# LinTempCont_4ch_V1_1.net
KiCad netlist of a schematic drawn in EAGLE
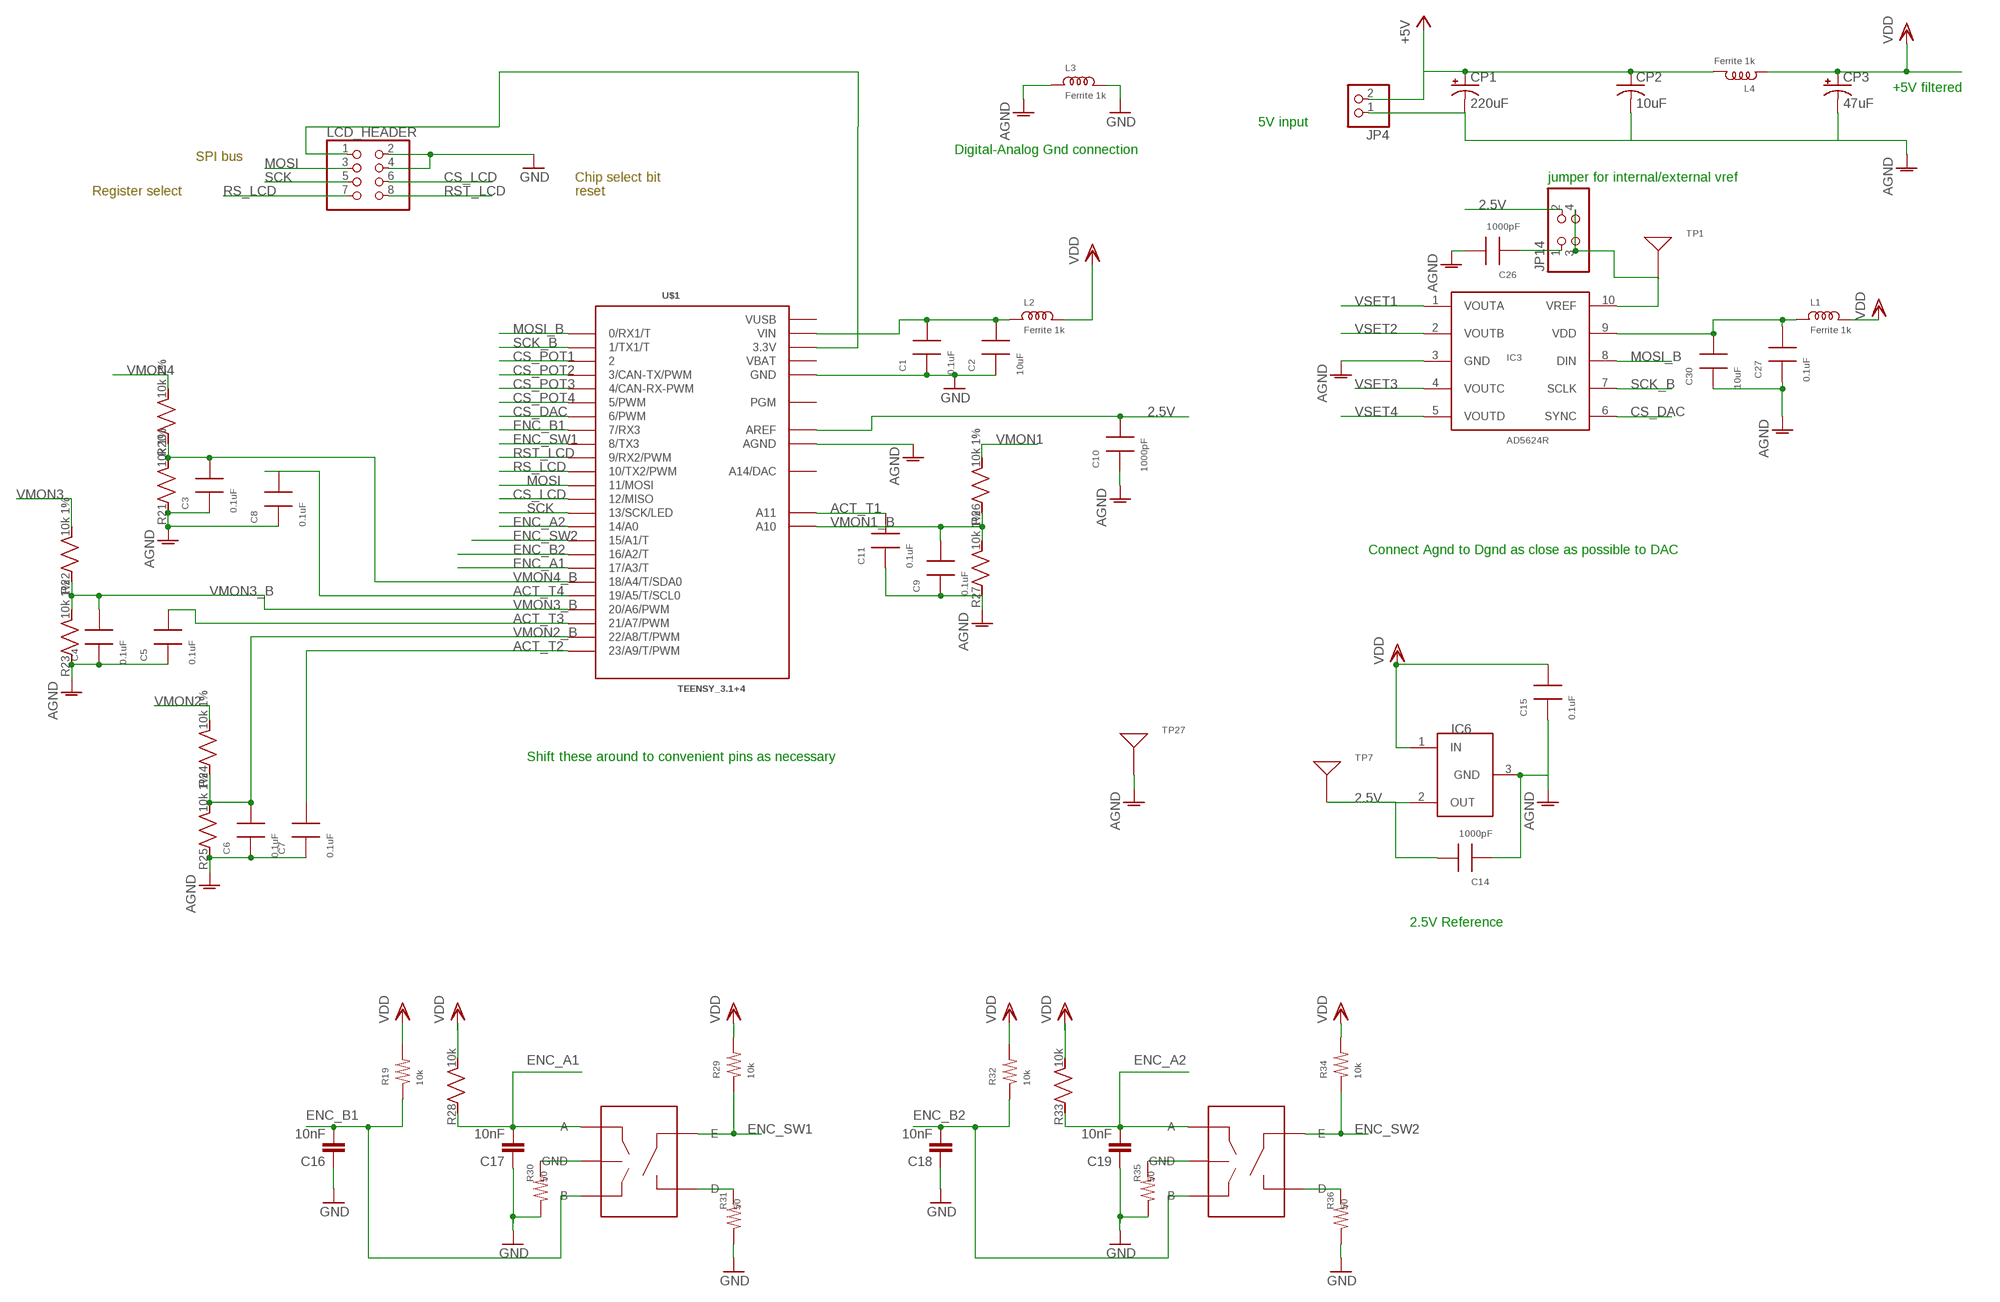
[diagram p0: schematic, sheet 1]
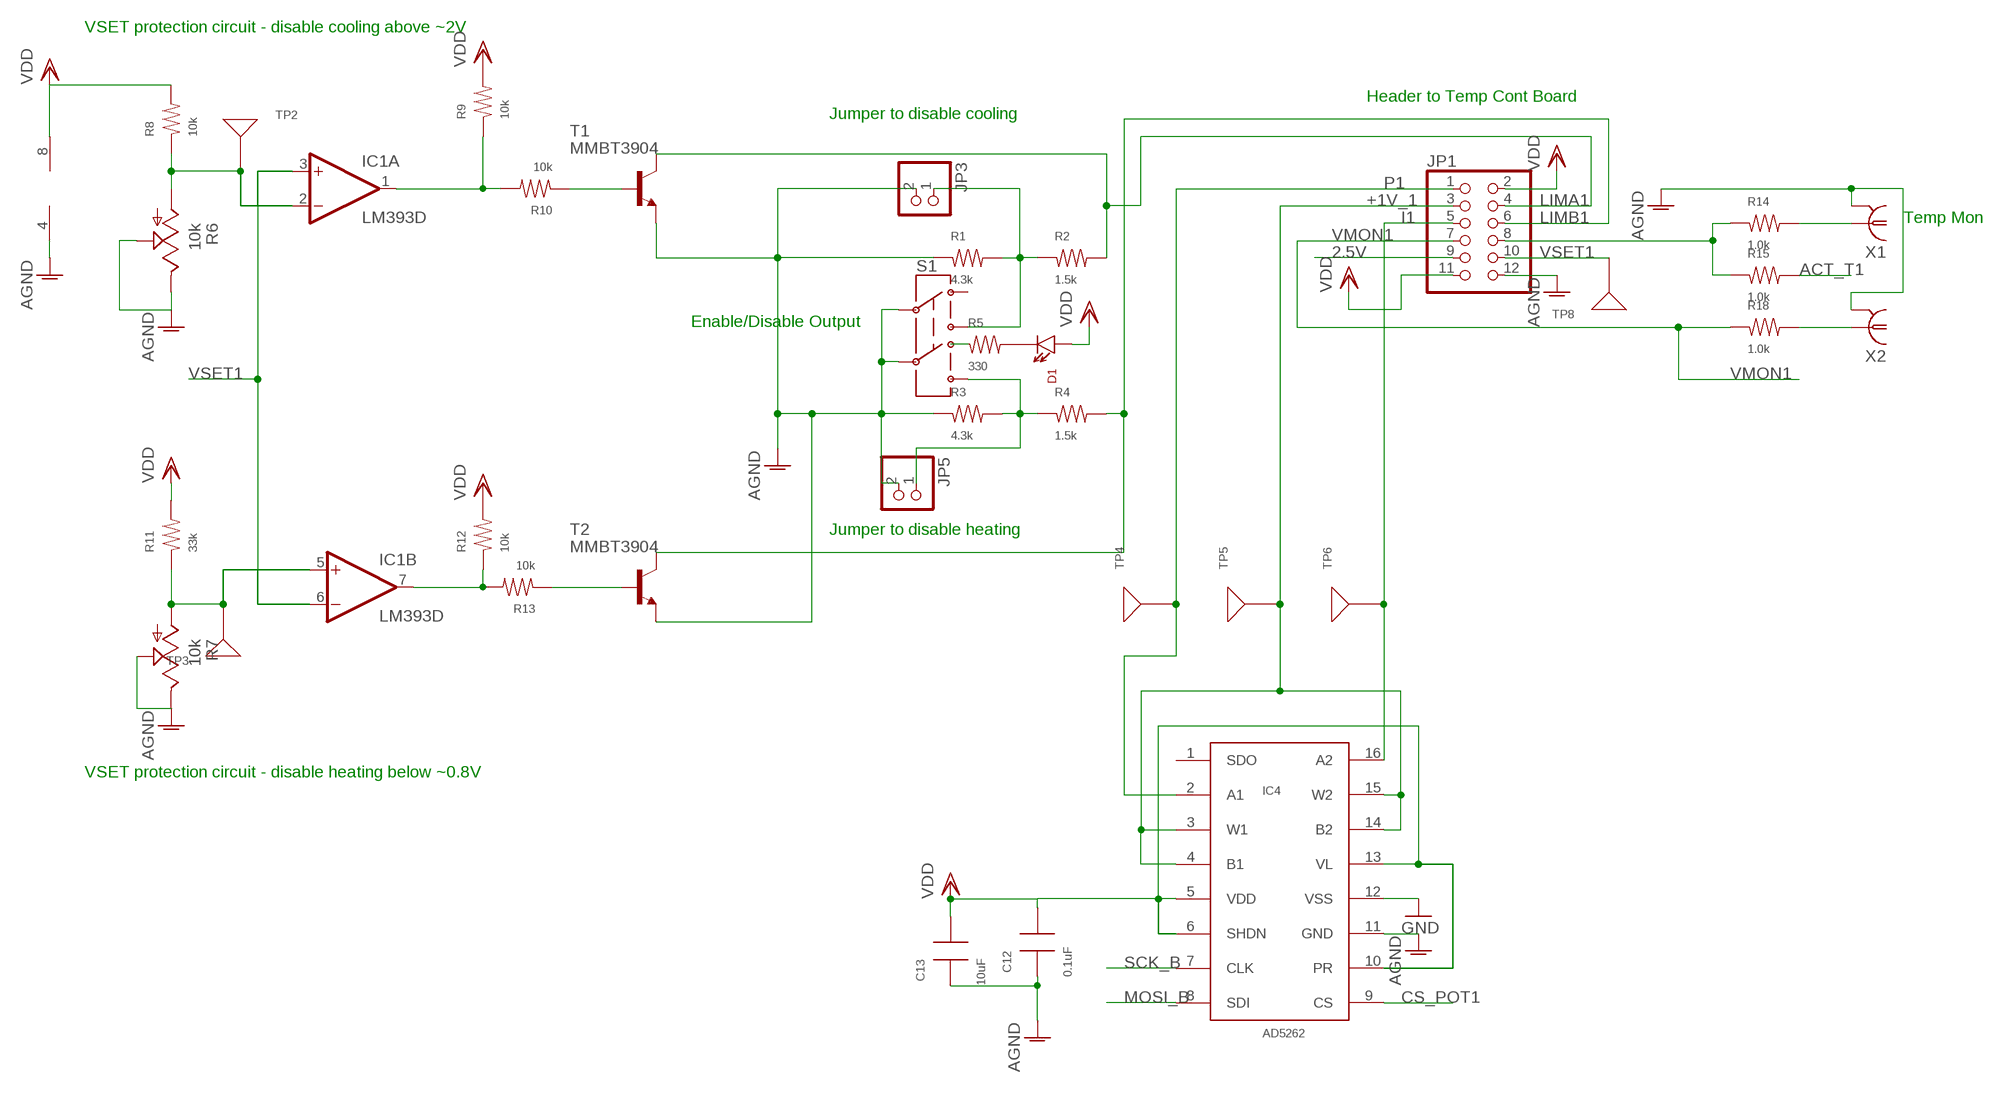
[diagram p1: schematic, sheet 2]
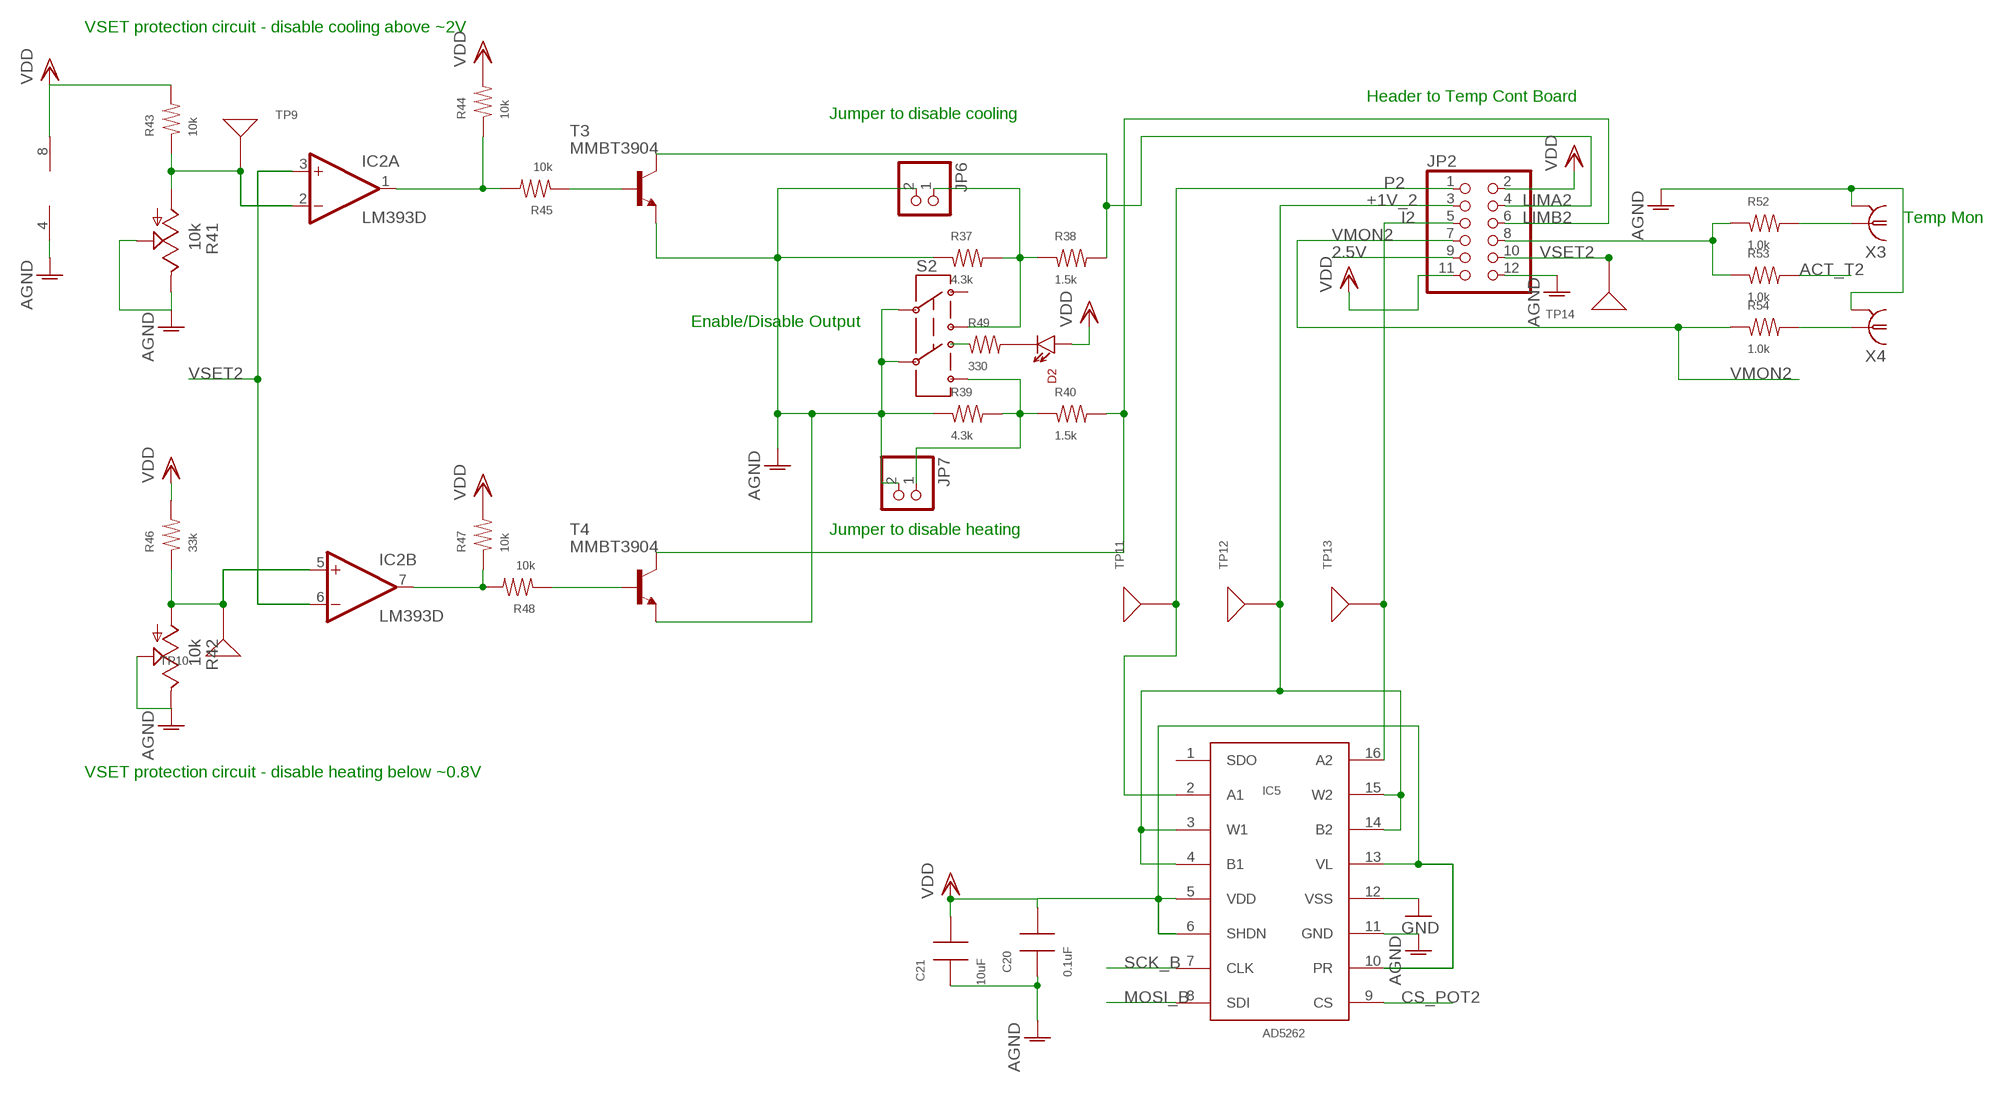
[diagram p2: schematic, sheet 3]
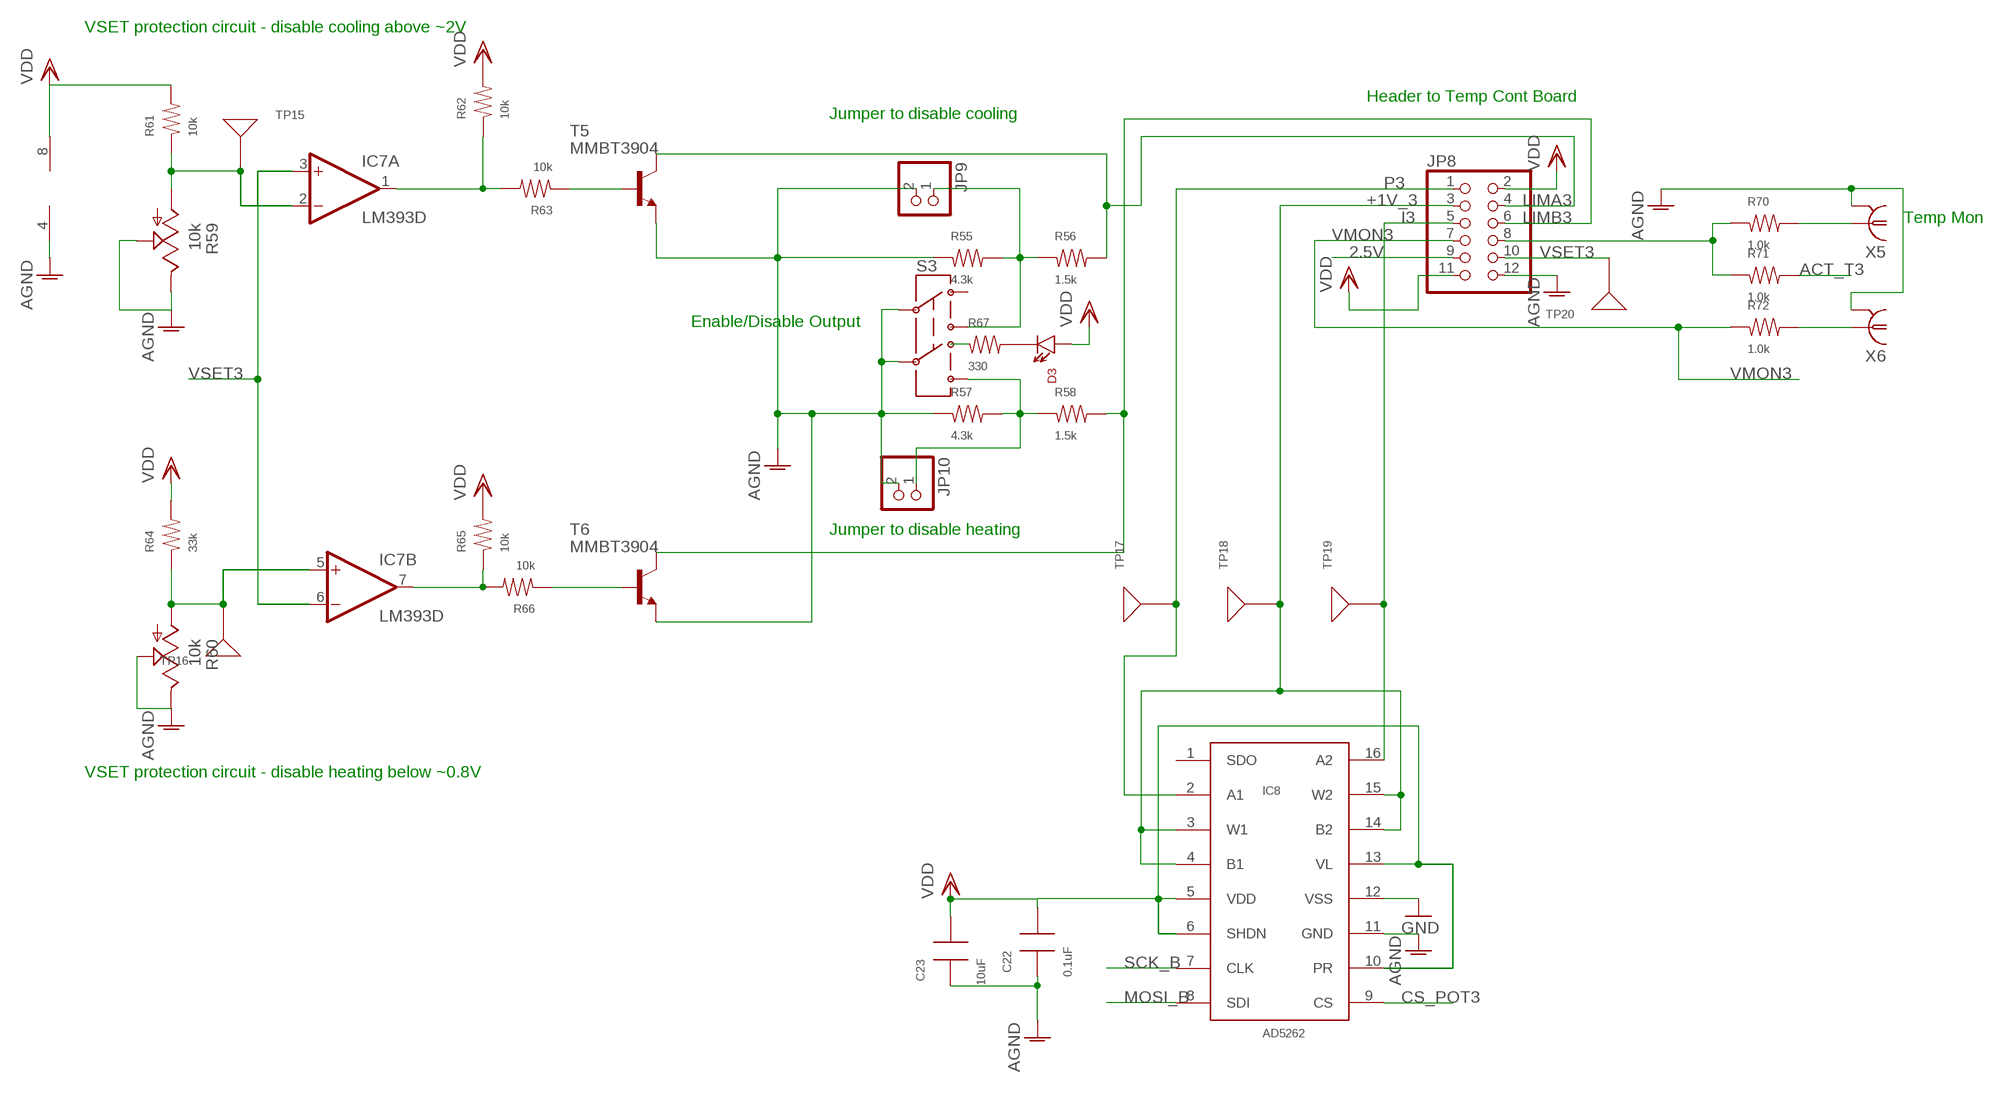
[diagram p3: schematic, sheet 4]
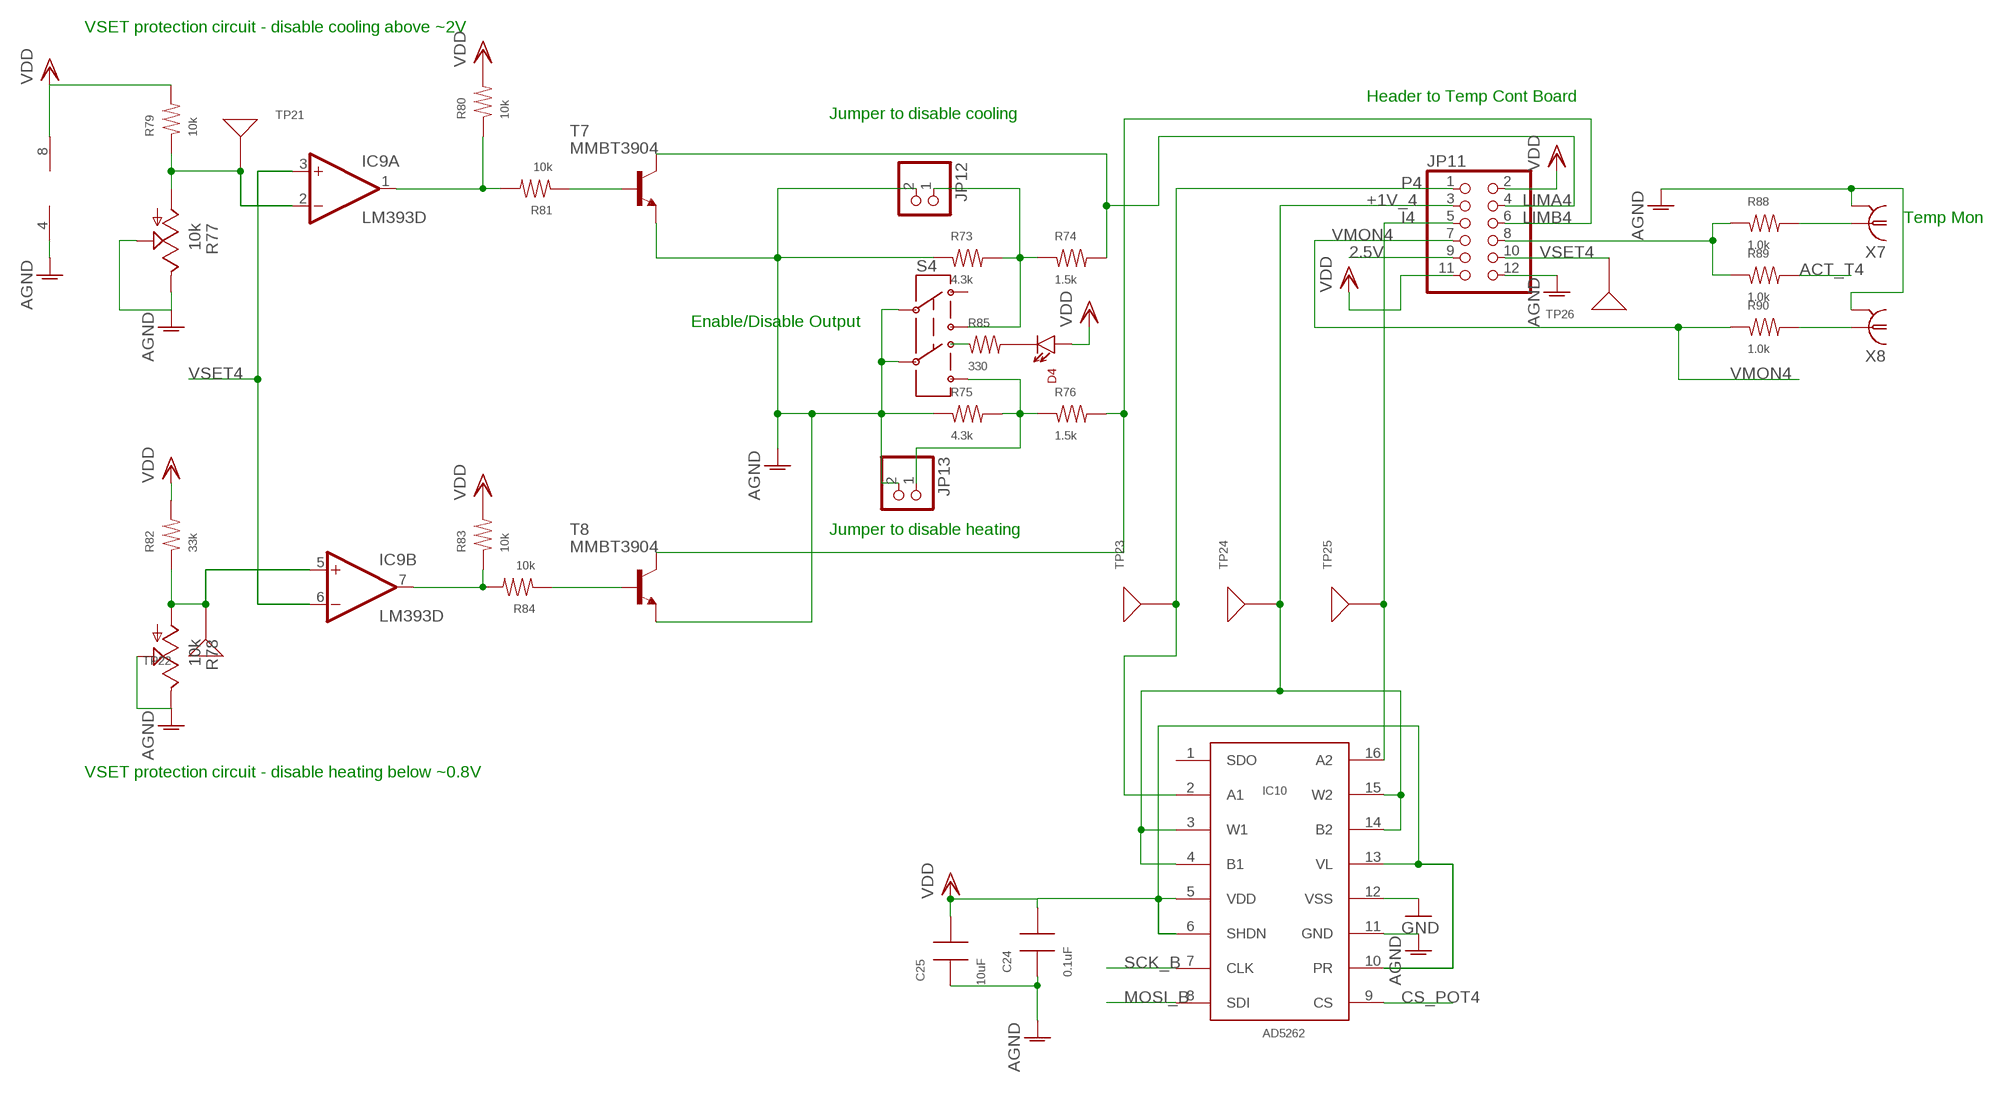
[diagram p4: schematic, sheet 5]

(export (version "E")
  (design (tool "Eeschema 10.0.6"))
  (components
    (comp (ref "C12")
      (value "0.1uF")
      (footprint "eagle-import:0603")
      (libsource (lib "eagle-import") (part "CAP0603"))
    )
    (comp (ref "C13")
      (value "10uF")
      (footprint "eagle-import:0805")
      (libsource (lib "eagle-import") (part "CAP0805"))
    )
    (comp (ref "D1")
      (value "LED/MINI-IND")
      (footprint "eagle-import:HLMP--F0010")
      (libsource (lib "eagle-import") (part "LED/MINI-IND"))
    )
    (comp (ref "IC1")
      (value "LM393D")
      (footprint "eagle-import:SO08")
      (libsource (lib "eagle-import") (part "LM393D"))
    )
    (comp (ref "IC4")
      (value "AD5262")
      (footprint "eagle-import:TSSOP16")
      (libsource (lib "eagle-import") (part "AD5262"))
    )
    (comp (ref "JP1")
      (value "PINHD-2X6/90")
      (footprint "eagle-import:2X06_90")
      (libsource (lib "eagle-import") (part "PINHD-2X6/90"))
    )
    (comp (ref "JP3")
      (value "PINHD-1X2")
      (footprint "eagle-import:1X02")
      (libsource (lib "eagle-import") (part "PINHD-1X2"))
    )
    (comp (ref "JP5")
      (value "PINHD-1X2")
      (footprint "eagle-import:1X02")
      (libsource (lib "eagle-import") (part "PINHD-1X2"))
    )
    (comp (ref "R1")
      (value "4.3k")
      (footprint "eagle-import:0603")
      (libsource (lib "eagle-import") (part "RES0603"))
    )
    (comp (ref "R2")
      (value "1.5k")
      (footprint "eagle-import:0603")
      (libsource (lib "eagle-import") (part "RES0603"))
    )
    (comp (ref "R3")
      (value "4.3k")
      (footprint "eagle-import:0603")
      (libsource (lib "eagle-import") (part "RES0603"))
    )
    (comp (ref "R4")
      (value "1.5k")
      (footprint "eagle-import:0603")
      (libsource (lib "eagle-import") (part "RES0603"))
    )
    (comp (ref "R5")
      (value "330")
      (footprint "eagle-import:0603")
      (libsource (lib "eagle-import") (part "RES0603"))
    )
    (comp (ref "R6")
      (value "10k")
      (footprint "eagle-import:64WPOT")
      (libsource (lib "eagle-import") (part "MODEL64_TRIMPOT/TOP-ADJ"))
    )
    (comp (ref "R7")
      (value "10k")
      (footprint "eagle-import:64WPOT")
      (libsource (lib "eagle-import") (part "MODEL64_TRIMPOT/TOP-ADJ"))
    )
    (comp (ref "R8")
      (value "10k")
      (footprint "eagle-import:0603")
      (libsource (lib "eagle-import") (part "RES0603"))
    )
    (comp (ref "R9")
      (value "10k")
      (footprint "eagle-import:0603")
      (libsource (lib "eagle-import") (part "RES0603"))
    )
    (comp (ref "R10")
      (value "10k")
      (footprint "eagle-import:0603")
      (libsource (lib "eagle-import") (part "RES0603"))
    )
    (comp (ref "R11")
      (value "33k")
      (footprint "eagle-import:0603")
      (libsource (lib "eagle-import") (part "RES0603"))
    )
    (comp (ref "R12")
      (value "10k")
      (footprint "eagle-import:0603")
      (libsource (lib "eagle-import") (part "RES0603"))
    )
    (comp (ref "R13")
      (value "10k")
      (footprint "eagle-import:0603")
      (libsource (lib "eagle-import") (part "RES0603"))
    )
    (comp (ref "R14")
      (value "1.0k")
      (footprint "eagle-import:0603")
      (libsource (lib "eagle-import") (part "RES0603"))
    )
    (comp (ref "R15")
      (value "1.0k")
      (footprint "eagle-import:0603")
      (libsource (lib "eagle-import") (part "RES0603"))
    )
    (comp (ref "R18")
      (value "1.0k")
      (footprint "eagle-import:0603")
      (libsource (lib "eagle-import") (part "RES0603"))
    )
    (comp (ref "S1")
      (value "SWITCH-DPDT/VER")
      (footprint "eagle-import:E-SWITCH-100-M7")
      (libsource (lib "eagle-import") (part "SWITCH-DPDT/VER"))
    )
    (comp (ref "T1")
      (value "MMBT3904")
      (footprint "eagle-import:SOT-23")
      (libsource (lib "eagle-import") (part "MMBT3904"))
    )
    (comp (ref "T2")
      (value "MMBT3904")
      (footprint "eagle-import:SOT-23")
      (libsource (lib "eagle-import") (part "MMBT3904"))
    )
    (comp (ref "TP2")
      (value "TESTPT")
      (footprint "eagle-import:1206TESTPAD")
      (libsource (lib "eagle-import") (part "TESTPT"))
    )
    (comp (ref "TP3")
      (value "TESTPT")
      (footprint "eagle-import:1206TESTPAD")
      (libsource (lib "eagle-import") (part "TESTPT"))
    )
    (comp (ref "TP4")
      (value "TESTPT")
      (footprint "eagle-import:1206TESTPAD")
      (libsource (lib "eagle-import") (part "TESTPT"))
    )
    (comp (ref "TP5")
      (value "TESTPT")
      (footprint "eagle-import:1206TESTPAD")
      (libsource (lib "eagle-import") (part "TESTPT"))
    )
    (comp (ref "TP6")
      (value "TESTPT")
      (footprint "eagle-import:1206TESTPAD")
      (libsource (lib "eagle-import") (part "TESTPT"))
    )
    (comp (ref "TP8")
      (value "TESTPT")
      (footprint "eagle-import:1206TESTPAD")
      (libsource (lib "eagle-import") (part "TESTPT"))
    )
    (comp (ref "X1")
      (value "BNC-H")
      (footprint "eagle-import:BNC90")
      (libsource (lib "eagle-import") (part "BNC-H"))
    )
    (comp (ref "X2")
      (value "BNC-H")
      (footprint "eagle-import:BNC90")
      (libsource (lib "eagle-import") (part "BNC-H"))
    )
    (comp (ref "C22")
      (value "0.1uF")
      (footprint "eagle-import:0603")
      (libsource (lib "eagle-import") (part "CAP0603"))
    )
    (comp (ref "C23")
      (value "10uF")
      (footprint "eagle-import:0805")
      (libsource (lib "eagle-import") (part "CAP0805"))
    )
    (comp (ref "D3")
      (value "LED/MINI-IND")
      (footprint "eagle-import:HLMP--F0010")
      (libsource (lib "eagle-import") (part "LED/MINI-IND"))
    )
    (comp (ref "IC7")
      (value "LM393D")
      (footprint "eagle-import:SO08")
      (libsource (lib "eagle-import") (part "LM393D"))
    )
    (comp (ref "IC8")
      (value "AD5262")
      (footprint "eagle-import:TSSOP16")
      (libsource (lib "eagle-import") (part "AD5262"))
    )
    (comp (ref "JP8")
      (value "PINHD-2X6/90")
      (footprint "eagle-import:2X06_90")
      (libsource (lib "eagle-import") (part "PINHD-2X6/90"))
    )
    (comp (ref "JP9")
      (value "PINHD-1X2")
      (footprint "eagle-import:1X02")
      (libsource (lib "eagle-import") (part "PINHD-1X2"))
    )
    (comp (ref "JP10")
      (value "PINHD-1X2")
      (footprint "eagle-import:1X02")
      (libsource (lib "eagle-import") (part "PINHD-1X2"))
    )
    (comp (ref "R55")
      (value "4.3k")
      (footprint "eagle-import:0603")
      (libsource (lib "eagle-import") (part "RES0603"))
    )
    (comp (ref "R56")
      (value "1.5k")
      (footprint "eagle-import:0603")
      (libsource (lib "eagle-import") (part "RES0603"))
    )
    (comp (ref "R57")
      (value "4.3k")
      (footprint "eagle-import:0603")
      (libsource (lib "eagle-import") (part "RES0603"))
    )
    (comp (ref "R58")
      (value "1.5k")
      (footprint "eagle-import:0603")
      (libsource (lib "eagle-import") (part "RES0603"))
    )
    (comp (ref "R59")
      (value "10k")
      (footprint "eagle-import:64WPOT")
      (libsource (lib "eagle-import") (part "MODEL64_TRIMPOT/TOP-ADJ"))
    )
    (comp (ref "R60")
      (value "10k")
      (footprint "eagle-import:64WPOT")
      (libsource (lib "eagle-import") (part "MODEL64_TRIMPOT/TOP-ADJ"))
    )
    (comp (ref "R61")
      (value "10k")
      (footprint "eagle-import:0603")
      (libsource (lib "eagle-import") (part "RES0603"))
    )
    (comp (ref "R62")
      (value "10k")
      (footprint "eagle-import:0603")
      (libsource (lib "eagle-import") (part "RES0603"))
    )
    (comp (ref "R63")
      (value "10k")
      (footprint "eagle-import:0603")
      (libsource (lib "eagle-import") (part "RES0603"))
    )
    (comp (ref "R64")
      (value "33k")
      (footprint "eagle-import:0603")
      (libsource (lib "eagle-import") (part "RES0603"))
    )
    (comp (ref "R65")
      (value "10k")
      (footprint "eagle-import:0603")
      (libsource (lib "eagle-import") (part "RES0603"))
    )
    (comp (ref "R66")
      (value "10k")
      (footprint "eagle-import:0603")
      (libsource (lib "eagle-import") (part "RES0603"))
    )
    (comp (ref "R67")
      (value "330")
      (footprint "eagle-import:0603")
      (libsource (lib "eagle-import") (part "RES0603"))
    )
    (comp (ref "R70")
      (value "1.0k")
      (footprint "eagle-import:0603")
      (libsource (lib "eagle-import") (part "RES0603"))
    )
    (comp (ref "R71")
      (value "1.0k")
      (footprint "eagle-import:0603")
      (libsource (lib "eagle-import") (part "RES0603"))
    )
    (comp (ref "R72")
      (value "1.0k")
      (footprint "eagle-import:0603")
      (libsource (lib "eagle-import") (part "RES0603"))
    )
    (comp (ref "S3")
      (value "SWITCH-DPDT/VER")
      (footprint "eagle-import:E-SWITCH-100-M7")
      (libsource (lib "eagle-import") (part "SWITCH-DPDT/VER"))
    )
    (comp (ref "T5")
      (value "MMBT3904")
      (footprint "eagle-import:SOT-23")
      (libsource (lib "eagle-import") (part "MMBT3904"))
    )
    (comp (ref "T6")
      (value "MMBT3904")
      (footprint "eagle-import:SOT-23")
      (libsource (lib "eagle-import") (part "MMBT3904"))
    )
    (comp (ref "TP15")
      (value "TESTPT")
      (footprint "eagle-import:1206TESTPAD")
      (libsource (lib "eagle-import") (part "TESTPT"))
    )
    (comp (ref "TP16")
      (value "TESTPT")
      (footprint "eagle-import:1206TESTPAD")
      (libsource (lib "eagle-import") (part "TESTPT"))
    )
    (comp (ref "TP17")
      (value "TESTPT")
      (footprint "eagle-import:1206TESTPAD")
      (libsource (lib "eagle-import") (part "TESTPT"))
    )
    (comp (ref "TP18")
      (value "TESTPT")
      (footprint "eagle-import:1206TESTPAD")
      (libsource (lib "eagle-import") (part "TESTPT"))
    )
    (comp (ref "TP19")
      (value "TESTPT")
      (footprint "eagle-import:1206TESTPAD")
      (libsource (lib "eagle-import") (part "TESTPT"))
    )
    (comp (ref "TP20")
      (value "TESTPT")
      (footprint "eagle-import:1206TESTPAD")
      (libsource (lib "eagle-import") (part "TESTPT"))
    )
    (comp (ref "X5")
      (value "BNC-H")
      (footprint "eagle-import:BNC90")
      (libsource (lib "eagle-import") (part "BNC-H"))
    )
    (comp (ref "X6")
      (value "BNC-H")
      (footprint "eagle-import:BNC90")
      (libsource (lib "eagle-import") (part "BNC-H"))
    )
    (comp (ref "C20")
      (value "0.1uF")
      (footprint "eagle-import:0603")
      (libsource (lib "eagle-import") (part "CAP0603"))
    )
    (comp (ref "C21")
      (value "10uF")
      (footprint "eagle-import:0805")
      (libsource (lib "eagle-import") (part "CAP0805"))
    )
    (comp (ref "D2")
      (value "LED/MINI-IND")
      (footprint "eagle-import:HLMP--F0010")
      (libsource (lib "eagle-import") (part "LED/MINI-IND"))
    )
    (comp (ref "IC2")
      (value "LM393D")
      (footprint "eagle-import:SO08")
      (libsource (lib "eagle-import") (part "LM393D"))
    )
    (comp (ref "IC5")
      (value "AD5262")
      (footprint "eagle-import:TSSOP16")
      (libsource (lib "eagle-import") (part "AD5262"))
    )
    (comp (ref "JP2")
      (value "PINHD-2X6/90")
      (footprint "eagle-import:2X06_90")
      (libsource (lib "eagle-import") (part "PINHD-2X6/90"))
    )
    (comp (ref "JP6")
      (value "PINHD-1X2")
      (footprint "eagle-import:1X02")
      (libsource (lib "eagle-import") (part "PINHD-1X2"))
    )
    (comp (ref "JP7")
      (value "PINHD-1X2")
      (footprint "eagle-import:1X02")
      (libsource (lib "eagle-import") (part "PINHD-1X2"))
    )
    (comp (ref "R37")
      (value "4.3k")
      (footprint "eagle-import:0603")
      (libsource (lib "eagle-import") (part "RES0603"))
    )
    (comp (ref "R38")
      (value "1.5k")
      (footprint "eagle-import:0603")
      (libsource (lib "eagle-import") (part "RES0603"))
    )
    (comp (ref "R39")
      (value "4.3k")
      (footprint "eagle-import:0603")
      (libsource (lib "eagle-import") (part "RES0603"))
    )
    (comp (ref "R40")
      (value "1.5k")
      (footprint "eagle-import:0603")
      (libsource (lib "eagle-import") (part "RES0603"))
    )
    (comp (ref "R41")
      (value "10k")
      (footprint "eagle-import:64WPOT")
      (libsource (lib "eagle-import") (part "MODEL64_TRIMPOT/TOP-ADJ"))
    )
    (comp (ref "R42")
      (value "10k")
      (footprint "eagle-import:64WPOT")
      (libsource (lib "eagle-import") (part "MODEL64_TRIMPOT/TOP-ADJ"))
    )
    (comp (ref "R43")
      (value "10k")
      (footprint "eagle-import:0603")
      (libsource (lib "eagle-import") (part "RES0603"))
    )
    (comp (ref "R44")
      (value "10k")
      (footprint "eagle-import:0603")
      (libsource (lib "eagle-import") (part "RES0603"))
    )
    (comp (ref "R45")
      (value "10k")
      (footprint "eagle-import:0603")
      (libsource (lib "eagle-import") (part "RES0603"))
    )
    (comp (ref "R46")
      (value "33k")
      (footprint "eagle-import:0603")
      (libsource (lib "eagle-import") (part "RES0603"))
    )
    (comp (ref "R47")
      (value "10k")
      (footprint "eagle-import:0603")
      (libsource (lib "eagle-import") (part "RES0603"))
    )
    (comp (ref "R48")
      (value "10k")
      (footprint "eagle-import:0603")
      (libsource (lib "eagle-import") (part "RES0603"))
    )
    (comp (ref "R49")
      (value "330")
      (footprint "eagle-import:0603")
      (libsource (lib "eagle-import") (part "RES0603"))
    )
    (comp (ref "R52")
      (value "1.0k")
      (footprint "eagle-import:0603")
      (libsource (lib "eagle-import") (part "RES0603"))
    )
    (comp (ref "R53")
      (value "1.0k")
      (footprint "eagle-import:0603")
      (libsource (lib "eagle-import") (part "RES0603"))
    )
    (comp (ref "R54")
      (value "1.0k")
      (footprint "eagle-import:0603")
      (libsource (lib "eagle-import") (part "RES0603"))
    )
    (comp (ref "S2")
      (value "SWITCH-DPDT/VER")
      (footprint "eagle-import:E-SWITCH-100-M7")
      (libsource (lib "eagle-import") (part "SWITCH-DPDT/VER"))
    )
    (comp (ref "T3")
      (value "MMBT3904")
      (footprint "eagle-import:SOT-23")
      (libsource (lib "eagle-import") (part "MMBT3904"))
    )
    (comp (ref "T4")
      (value "MMBT3904")
      (footprint "eagle-import:SOT-23")
      (libsource (lib "eagle-import") (part "MMBT3904"))
    )
    (comp (ref "TP9")
      (value "TESTPT")
      (footprint "eagle-import:1206TESTPAD")
      (libsource (lib "eagle-import") (part "TESTPT"))
    )
    (comp (ref "TP10")
      (value "TESTPT")
      (footprint "eagle-import:1206TESTPAD")
      (libsource (lib "eagle-import") (part "TESTPT"))
    )
    (comp (ref "TP11")
      (value "TESTPT")
      (footprint "eagle-import:1206TESTPAD")
      (libsource (lib "eagle-import") (part "TESTPT"))
    )
    (comp (ref "TP12")
      (value "TESTPT")
      (footprint "eagle-import:1206TESTPAD")
      (libsource (lib "eagle-import") (part "TESTPT"))
    )
    (comp (ref "TP13")
      (value "TESTPT")
      (footprint "eagle-import:1206TESTPAD")
      (libsource (lib "eagle-import") (part "TESTPT"))
    )
    (comp (ref "TP14")
      (value "TESTPT")
      (footprint "eagle-import:1206TESTPAD")
      (libsource (lib "eagle-import") (part "TESTPT"))
    )
    (comp (ref "X3")
      (value "BNC-H")
      (footprint "eagle-import:BNC90")
      (libsource (lib "eagle-import") (part "BNC-H"))
    )
    (comp (ref "X4")
      (value "BNC-H")
      (footprint "eagle-import:BNC90")
      (libsource (lib "eagle-import") (part "BNC-H"))
    )
    (comp (ref "C1")
      (value "0.1uF")
      (footprint "eagle-import:0603")
      (libsource (lib "eagle-import") (part "CAP0603"))
    )
    (comp (ref "C2")
      (value "10uF")
      (footprint "eagle-import:0805")
      (libsource (lib "eagle-import") (part "CAP0805"))
    )
    (comp (ref "C3")
      (value "0.1uF")
      (footprint "eagle-import:0603")
      (libsource (lib "eagle-import") (part "CAP0603"))
    )
    (comp (ref "C4")
      (value "0.1uF")
      (footprint "eagle-import:0603")
      (libsource (lib "eagle-import") (part "CAP0603"))
    )
    (comp (ref "C5")
      (value "0.1uF")
      (footprint "eagle-import:0603")
      (libsource (lib "eagle-import") (part "CAP0603"))
    )
    (comp (ref "C6")
      (value "0.1uF")
      (footprint "eagle-import:0603")
      (libsource (lib "eagle-import") (part "CAP0603"))
    )
    (comp (ref "C7")
      (value "0.1uF")
      (footprint "eagle-import:0603")
      (libsource (lib "eagle-import") (part "CAP0603"))
    )
    (comp (ref "C8")
      (value "0.1uF")
      (footprint "eagle-import:0603")
      (libsource (lib "eagle-import") (part "CAP0603"))
    )
    (comp (ref "C9")
      (value "0.1uF")
      (footprint "eagle-import:0603")
      (libsource (lib "eagle-import") (part "CAP0603"))
    )
    (comp (ref "C10")
      (value "1000pF")
      (footprint "eagle-import:0603")
      (libsource (lib "eagle-import") (part "CAP0603"))
    )
    (comp (ref "C11")
      (value "0.1uF")
      (footprint "eagle-import:0603")
      (libsource (lib "eagle-import") (part "CAP0603"))
    )
    (comp (ref "C14")
      (value "1000pF")
      (footprint "eagle-import:0603")
      (libsource (lib "eagle-import") (part "CAP0603"))
    )
    (comp (ref "C15")
      (value "0.1uF")
      (footprint "eagle-import:0603")
      (libsource (lib "eagle-import") (part "CAP0603"))
    )
    (comp (ref "C16")
      (value "10nF")
      (footprint "eagle-import:C0603")
      (libsource (lib "eagle-import") (part "C-EUC0603"))
    )
    (comp (ref "C17")
      (value "10nF")
      (footprint "eagle-import:C0603")
      (libsource (lib "eagle-import") (part "C-EUC0603"))
    )
    (comp (ref "C18")
      (value "10nF")
      (footprint "eagle-import:C0603")
      (libsource (lib "eagle-import") (part "C-EUC0603"))
    )
    (comp (ref "C19")
      (value "10nF")
      (footprint "eagle-import:C0603")
      (libsource (lib "eagle-import") (part "C-EUC0603"))
    )
    (comp (ref "C26")
      (value "1000pF")
      (footprint "eagle-import:0603")
      (libsource (lib "eagle-import") (part "CAP0603"))
    )
    (comp (ref "C27")
      (value "0.1uF")
      (footprint "eagle-import:0603")
      (libsource (lib "eagle-import") (part "CAP0603"))
    )
    (comp (ref "C30")
      (value "10uF")
      (footprint "eagle-import:0805")
      (libsource (lib "eagle-import") (part "CAP0805"))
    )
    (comp (ref "CP1")
      (value "220uF")
      (footprint "eagle-import:PANASONIC_F")
      (libsource (lib "eagle-import") (part "CPOL-USF"))
    )
    (comp (ref "CP2")
      (value "10uF")
      (footprint "eagle-import:C0805K")
      (libsource (lib "eagle-import") (part "C-USC0805K"))
    )
    (comp (ref "CP3")
      (value "47uF")
      (footprint "eagle-import:CT7343")
      (libsource (lib "eagle-import") (part "CPOL-USCT7343"))
    )
    (comp (ref "ENC1")
      (value "PEC09")
      (footprint "eagle-import:PEC092320FS")
      (libsource (lib "eagle-import") (part "PEC09"))
    )
    (comp (ref "ENC2")
      (value "PEC09")
      (footprint "eagle-import:PEC092320FS")
      (libsource (lib "eagle-import") (part "PEC09"))
    )
    (comp (ref "IC3")
      (value "AD5624R")
      (footprint "eagle-import:MSOP10")
      (libsource (lib "eagle-import") (part "AD5624R"))
    )
    (comp (ref "IC6")
      (value "TS6001")
      (footprint "eagle-import:SOT-23")
      (libsource (lib "eagle-import") (part "TS6001"))
    )
    (comp (ref "JP4")
      (value "SCRWTRM-1X2")
      (footprint "eagle-import:1X02_SCRWTRM")
      (libsource (lib "eagle-import") (part "SCRWTRM-1X2"))
    )
    (comp (ref "JP14")
      (value "PINHD-2X2")
      (footprint "eagle-import:2X02")
      (libsource (lib "eagle-import") (part "PINHD-2X2"))
    )
    (comp (ref "L1")
      (value "Ferrite 1k")
      (footprint "eagle-import:0805")
      (libsource (lib "eagle-import") (part "INDUCTOR-0805"))
    )
    (comp (ref "L2")
      (value "Ferrite 1k")
      (footprint "eagle-import:0805")
      (libsource (lib "eagle-import") (part "INDUCTOR-0805"))
    )
    (comp (ref "L3")
      (value "Ferrite 1k")
      (footprint "eagle-import:0805")
      (libsource (lib "eagle-import") (part "INDUCTOR-0805"))
    )
    (comp (ref "L4")
      (value "Ferrite 1k")
      (footprint "eagle-import:0805")
      (libsource (lib "eagle-import") (part "INDUCTOR-0805"))
    )
    (comp (ref "LCD_HEADER")
      (value "PINHD-2X4-SHROUD")
      (footprint "eagle-import:ML08")
      (libsource (lib "eagle-import") (part "PINHD-2X4-SHROUD"))
    )
    (comp (ref "R19")
      (value "10k")
      (footprint "eagle-import:0603")
      (libsource (lib "eagle-import") (part "RES0603"))
    )
    (comp (ref "R20")
      (value "10k 1%")
      (footprint "eagle-import:R_0603")
      (libsource (lib "eagle-import") (part "R_SMDR0603"))
    )
    (comp (ref "R21")
      (value "10k 1%")
      (footprint "eagle-import:R_0603")
      (libsource (lib "eagle-import") (part "R_SMDR0603"))
    )
    (comp (ref "R22")
      (value "10k 1%")
      (footprint "eagle-import:R_0603")
      (libsource (lib "eagle-import") (part "R_SMDR0603"))
    )
    (comp (ref "R23")
      (value "10k 1%")
      (footprint "eagle-import:R_0603")
      (libsource (lib "eagle-import") (part "R_SMDR0603"))
    )
    (comp (ref "R24")
      (value "10k 1%")
      (footprint "eagle-import:R_0603")
      (libsource (lib "eagle-import") (part "R_SMDR0603"))
    )
    (comp (ref "R25")
      (value "10k 1%")
      (footprint "eagle-import:R_0603")
      (libsource (lib "eagle-import") (part "R_SMDR0603"))
    )
    (comp (ref "R26")
      (value "10k 1%")
      (footprint "eagle-import:R_0603")
      (libsource (lib "eagle-import") (part "R_SMDR0603"))
    )
    (comp (ref "R27")
      (value "10k 1%")
      (footprint "eagle-import:R_0603")
      (libsource (lib "eagle-import") (part "R_SMDR0603"))
    )
    (comp (ref "R28")
      (value "10k")
      (footprint "eagle-import:R_0603")
      (libsource (lib "eagle-import") (part "R_SMDR0603"))
    )
    (comp (ref "R29")
      (value "10k")
      (footprint "eagle-import:0603")
      (libsource (lib "eagle-import") (part "RES0603"))
    )
    (comp (ref "R30")
      (value "50")
      (footprint "eagle-import:0603")
      (libsource (lib "eagle-import") (part "RES0603"))
    )
    (comp (ref "R31")
      (value "50")
      (footprint "eagle-import:0603")
      (libsource (lib "eagle-import") (part "RES0603"))
    )
    (comp (ref "R32")
      (value "10k")
      (footprint "eagle-import:0603")
      (libsource (lib "eagle-import") (part "RES0603"))
    )
    (comp (ref "R33")
      (value "10k")
      (footprint "eagle-import:R_0603")
      (libsource (lib "eagle-import") (part "R_SMDR0603"))
    )
    (comp (ref "R34")
      (value "10k")
      (footprint "eagle-import:0603")
      (libsource (lib "eagle-import") (part "RES0603"))
    )
    (comp (ref "R35")
      (value "50")
      (footprint "eagle-import:0603")
      (libsource (lib "eagle-import") (part "RES0603"))
    )
    (comp (ref "R36")
      (value "50")
      (footprint "eagle-import:0603")
      (libsource (lib "eagle-import") (part "RES0603"))
    )
    (comp (ref "TP1")
      (value "TESTPT")
      (footprint "eagle-import:1206TESTPAD")
      (libsource (lib "eagle-import") (part "TESTPT"))
    )
    (comp (ref "TP7")
      (value "TESTPT")
      (footprint "eagle-import:1206TESTPAD")
      (libsource (lib "eagle-import") (part "TESTPT"))
    )
    (comp (ref "TP27")
      (value "TESTPT")
      (footprint "eagle-import:1206TESTPAD")
      (libsource (lib "eagle-import") (part "TESTPT"))
    )
    (comp (ref "U$1")
      (value "TEENSY_3.1+4")
      (footprint "eagle-import:TEENSY_3.1+4")
      (libsource (lib "eagle-import") (part "TEENSY_3.1+4"))
    )
    (comp (ref "C24")
      (value "0.1uF")
      (footprint "eagle-import:0603")
      (libsource (lib "eagle-import") (part "CAP0603"))
    )
    (comp (ref "C25")
      (value "10uF")
      (footprint "eagle-import:0805")
      (libsource (lib "eagle-import") (part "CAP0805"))
    )
    (comp (ref "D4")
      (value "LED/MINI-IND")
      (footprint "eagle-import:HLMP--F0010")
      (libsource (lib "eagle-import") (part "LED/MINI-IND"))
    )
    (comp (ref "IC9")
      (value "LM393D")
      (footprint "eagle-import:SO08")
      (libsource (lib "eagle-import") (part "LM393D"))
    )
    (comp (ref "IC10")
      (value "AD5262")
      (footprint "eagle-import:TSSOP16")
      (libsource (lib "eagle-import") (part "AD5262"))
    )
    (comp (ref "JP11")
      (value "PINHD-2X6/90")
      (footprint "eagle-import:2X06_90")
      (libsource (lib "eagle-import") (part "PINHD-2X6/90"))
    )
    (comp (ref "JP12")
      (value "PINHD-1X2")
      (footprint "eagle-import:1X02")
      (libsource (lib "eagle-import") (part "PINHD-1X2"))
    )
    (comp (ref "JP13")
      (value "PINHD-1X2")
      (footprint "eagle-import:1X02")
      (libsource (lib "eagle-import") (part "PINHD-1X2"))
    )
    (comp (ref "R73")
      (value "4.3k")
      (footprint "eagle-import:0603")
      (libsource (lib "eagle-import") (part "RES0603"))
    )
    (comp (ref "R74")
      (value "1.5k")
      (footprint "eagle-import:0603")
      (libsource (lib "eagle-import") (part "RES0603"))
    )
    (comp (ref "R75")
      (value "4.3k")
      (footprint "eagle-import:0603")
      (libsource (lib "eagle-import") (part "RES0603"))
    )
    (comp (ref "R76")
      (value "1.5k")
      (footprint "eagle-import:0603")
      (libsource (lib "eagle-import") (part "RES0603"))
    )
    (comp (ref "R77")
      (value "10k")
      (footprint "eagle-import:64WPOT")
      (libsource (lib "eagle-import") (part "MODEL64_TRIMPOT/TOP-ADJ"))
    )
    (comp (ref "R78")
      (value "10k")
      (footprint "eagle-import:64WPOT")
      (libsource (lib "eagle-import") (part "MODEL64_TRIMPOT/TOP-ADJ"))
    )
    (comp (ref "R79")
      (value "10k")
      (footprint "eagle-import:0603")
      (libsource (lib "eagle-import") (part "RES0603"))
    )
    (comp (ref "R80")
      (value "10k")
      (footprint "eagle-import:0603")
      (libsource (lib "eagle-import") (part "RES0603"))
    )
    (comp (ref "R81")
      (value "10k")
      (footprint "eagle-import:0603")
      (libsource (lib "eagle-import") (part "RES0603"))
    )
    (comp (ref "R82")
      (value "33k")
      (footprint "eagle-import:0603")
      (libsource (lib "eagle-import") (part "RES0603"))
    )
    (comp (ref "R83")
      (value "10k")
      (footprint "eagle-import:0603")
      (libsource (lib "eagle-import") (part "RES0603"))
    )
    (comp (ref "R84")
      (value "10k")
      (footprint "eagle-import:0603")
      (libsource (lib "eagle-import") (part "RES0603"))
    )
    (comp (ref "R85")
      (value "330")
      (footprint "eagle-import:0603")
      (libsource (lib "eagle-import") (part "RES0603"))
    )
    (comp (ref "R88")
      (value "1.0k")
      (footprint "eagle-import:0603")
      (libsource (lib "eagle-import") (part "RES0603"))
    )
    (comp (ref "R89")
      (value "1.0k")
      (footprint "eagle-import:0603")
      (libsource (lib "eagle-import") (part "RES0603"))
    )
    (comp (ref "R90")
      (value "1.0k")
      (footprint "eagle-import:0603")
      (libsource (lib "eagle-import") (part "RES0603"))
    )
    (comp (ref "S4")
      (value "SWITCH-DPDT/VER")
      (footprint "eagle-import:E-SWITCH-100-M7")
      (libsource (lib "eagle-import") (part "SWITCH-DPDT/VER"))
    )
    (comp (ref "T7")
      (value "MMBT3904")
      (footprint "eagle-import:SOT-23")
      (libsource (lib "eagle-import") (part "MMBT3904"))
    )
    (comp (ref "T8")
      (value "MMBT3904")
      (footprint "eagle-import:SOT-23")
      (libsource (lib "eagle-import") (part "MMBT3904"))
    )
    (comp (ref "TP21")
      (value "TESTPT")
      (footprint "eagle-import:1206TESTPAD")
      (libsource (lib "eagle-import") (part "TESTPT"))
    )
    (comp (ref "TP22")
      (value "TESTPT")
      (footprint "eagle-import:1206TESTPAD")
      (libsource (lib "eagle-import") (part "TESTPT"))
    )
    (comp (ref "TP23")
      (value "TESTPT")
      (footprint "eagle-import:1206TESTPAD")
      (libsource (lib "eagle-import") (part "TESTPT"))
    )
    (comp (ref "TP24")
      (value "TESTPT")
      (footprint "eagle-import:1206TESTPAD")
      (libsource (lib "eagle-import") (part "TESTPT"))
    )
    (comp (ref "TP25")
      (value "TESTPT")
      (footprint "eagle-import:1206TESTPAD")
      (libsource (lib "eagle-import") (part "TESTPT"))
    )
    (comp (ref "TP26")
      (value "TESTPT")
      (footprint "eagle-import:1206TESTPAD")
      (libsource (lib "eagle-import") (part "TESTPT"))
    )
    (comp (ref "X7")
      (value "BNC-H")
      (footprint "eagle-import:BNC90")
      (libsource (lib "eagle-import") (part "BNC-H"))
    )
    (comp (ref "X8")
      (value "BNC-H")
      (footprint "eagle-import:BNC90")
      (libsource (lib "eagle-import") (part "BNC-H"))
    )
  )
  (nets
    (net (code "1") (name "+1V_1") (class "Default")
      (node (ref "IC4") (pin "14") (pinfunction "B2_14") (pintype "bidirectional"))
      (node (ref "IC4") (pin "15") (pinfunction "W2_15") (pintype "bidirectional"))
      (node (ref "IC4") (pin "3") (pinfunction "W1_3") (pintype "bidirectional"))
      (node (ref "IC4") (pin "4") (pinfunction "B1_4") (pintype "bidirectional"))
      (node (ref "JP1") (pin "3") (pinfunction "3_3") (pintype "passive"))
      (node (ref "TP5") (pin "P$1") (pinfunction "P$1_P$1") (pintype "bidirectional"))
    )
    (net (code "2") (name "+1V_2") (class "Default")
      (node (ref "IC5") (pin "14") (pinfunction "B2_14") (pintype "bidirectional"))
      (node (ref "IC5") (pin "15") (pinfunction "W2_15") (pintype "bidirectional"))
      (node (ref "IC5") (pin "3") (pinfunction "W1_3") (pintype "bidirectional"))
      (node (ref "IC5") (pin "4") (pinfunction "B1_4") (pintype "bidirectional"))
      (node (ref "JP2") (pin "3") (pinfunction "3_3") (pintype "passive"))
      (node (ref "TP12") (pin "P$1") (pinfunction "P$1_P$1") (pintype "bidirectional"))
    )
    (net (code "3") (name "+1V_3") (class "Default")
      (node (ref "IC8") (pin "14") (pinfunction "B2_14") (pintype "bidirectional"))
      (node (ref "IC8") (pin "15") (pinfunction "W2_15") (pintype "bidirectional"))
      (node (ref "IC8") (pin "3") (pinfunction "W1_3") (pintype "bidirectional"))
      (node (ref "IC8") (pin "4") (pinfunction "B1_4") (pintype "bidirectional"))
      (node (ref "JP8") (pin "3") (pinfunction "3_3") (pintype "passive"))
      (node (ref "TP18") (pin "P$1") (pinfunction "P$1_P$1") (pintype "bidirectional"))
    )
    (net (code "4") (name "+1V_4") (class "Default")
      (node (ref "IC10") (pin "14") (pinfunction "B2_14") (pintype "bidirectional"))
      (node (ref "IC10") (pin "15") (pinfunction "W2_15") (pintype "bidirectional"))
      (node (ref "IC10") (pin "3") (pinfunction "W1_3") (pintype "bidirectional"))
      (node (ref "IC10") (pin "4") (pinfunction "B1_4") (pintype "bidirectional"))
      (node (ref "JP11") (pin "3") (pinfunction "3_3") (pintype "passive"))
      (node (ref "TP24") (pin "P$1") (pinfunction "P$1_P$1") (pintype "bidirectional"))
    )
    (net (code "5") (name "+5V") (class "Default")
      (node (ref "CP1") (pin "+") (pinfunction "+_+") (pintype "passive"))
      (node (ref "CP2") (pin "1") (pinfunction "1_1") (pintype "passive"))
      (node (ref "JP4") (pin "2") (pinfunction "2_2") (pintype "passive"))
      (node (ref "L4") (pin "2") (pinfunction "P$2_2") (pintype "passive"))
    )
    (net (code "6") (name "2.5V") (class "Default")
      (node (ref "C10") (pin "2") (pinfunction "P$2_2") (pintype "passive"))
      (node (ref "C14") (pin "2") (pinfunction "P$2_2") (pintype "passive"))
      (node (ref "IC6") (pin "2") (pinfunction "OUT_2") (pintype "bidirectional"))
      (node (ref "JP1") (pin "9") (pinfunction "9_9") (pintype "passive"))
      (node (ref "JP11") (pin "9") (pinfunction "9_9") (pintype "passive"))
      (node (ref "JP14") (pin "2") (pinfunction "2_2") (pintype "passive"))
      (node (ref "JP2") (pin "9") (pinfunction "9_9") (pintype "passive"))
      (node (ref "JP8") (pin "9") (pinfunction "9_9") (pintype "passive"))
      (node (ref "TP7") (pin "P$1") (pinfunction "P$1_P$1") (pintype "bidirectional"))
      (node (ref "U$1") (pin "AREF") (pinfunction "AREF_AREF") (pintype "power_in"))
    )
    (net (code "7") (name "ACT_T1") (class "Default")
      (node (ref "C11") (pin "2") (pinfunction "P$2_2") (pintype "passive"))
      (node (ref "R15") (pin "2") (pinfunction "P$2_2") (pintype "passive"))
      (node (ref "U$1") (pin "A11") (pinfunction "A11_A11") (pintype "bidirectional"))
    )
    (net (code "8") (name "ACT_T2") (class "Default")
      (node (ref "C7") (pin "2") (pinfunction "P$2_2") (pintype "passive"))
      (node (ref "R53") (pin "2") (pinfunction "P$2_2") (pintype "passive"))
      (node (ref "U$1") (pin "23/A9") (pinfunction "23/A9/T/PWM_23/A9") (pintype "bidirectional"))
    )
    (net (code "9") (name "ACT_T3") (class "Default")
      (node (ref "C5") (pin "2") (pinfunction "P$2_2") (pintype "passive"))
      (node (ref "R71") (pin "2") (pinfunction "P$2_2") (pintype "passive"))
      (node (ref "U$1") (pin "21/A7") (pinfunction "21/A7/PWM_21/A7") (pintype "bidirectional"))
    )
    (net (code "10") (name "ACT_T4") (class "Default")
      (node (ref "C8") (pin "2") (pinfunction "P$2_2") (pintype "passive"))
      (node (ref "R89") (pin "2") (pinfunction "P$2_2") (pintype "passive"))
      (node (ref "U$1") (pin "19/A5") (pinfunction "19/A5/T/SCL0_19/A5") (pintype "bidirectional"))
    )
    (net (code "11") (name "AGND") (class "Default")
      (node (ref "C10") (pin "1") (pinfunction "P$1_1") (pintype "passive"))
      (node (ref "C11") (pin "1") (pinfunction "P$1_1") (pintype "passive"))
      (node (ref "C12") (pin "1") (pinfunction "P$1_1") (pintype "passive"))
      (node (ref "C13") (pin "1") (pinfunction "P$1_1") (pintype "passive"))
      (node (ref "C14") (pin "1") (pinfunction "P$1_1") (pintype "passive"))
      (node (ref "C15") (pin "1") (pinfunction "P$1_1") (pintype "passive"))
      (node (ref "C20") (pin "1") (pinfunction "P$1_1") (pintype "passive"))
      (node (ref "C21") (pin "1") (pinfunction "P$1_1") (pintype "passive"))
      (node (ref "C22") (pin "1") (pinfunction "P$1_1") (pintype "passive"))
      (node (ref "C23") (pin "1") (pinfunction "P$1_1") (pintype "passive"))
      (node (ref "C24") (pin "1") (pinfunction "P$1_1") (pintype "passive"))
      (node (ref "C25") (pin "1") (pinfunction "P$1_1") (pintype "passive"))
      (node (ref "C26") (pin "2") (pinfunction "P$2_2") (pintype "passive"))
      (node (ref "C27") (pin "1") (pinfunction "P$1_1") (pintype "passive"))
      (node (ref "C3") (pin "1") (pinfunction "P$1_1") (pintype "passive"))
      (node (ref "C30") (pin "1") (pinfunction "P$1_1") (pintype "passive"))
      (node (ref "C4") (pin "1") (pinfunction "P$1_1") (pintype "passive"))
      (node (ref "C5") (pin "1") (pinfunction "P$1_1") (pintype "passive"))
      (node (ref "C6") (pin "1") (pinfunction "P$1_1") (pintype "passive"))
      (node (ref "C7") (pin "1") (pinfunction "P$1_1") (pintype "passive"))
      (node (ref "C8") (pin "1") (pinfunction "P$1_1") (pintype "passive"))
      (node (ref "C9") (pin "1") (pinfunction "P$1_1") (pintype "passive"))
      (node (ref "CP1") (pin "-") (pinfunction "-_-") (pintype "passive"))
      (node (ref "CP2") (pin "2") (pinfunction "2_2") (pintype "passive"))
      (node (ref "CP3") (pin "-") (pinfunction "-_-") (pintype "passive"))
      (node (ref "IC1") (pin "4") (pinfunction "V-_4") (pintype "power_in"))
      (node (ref "IC10") (pin "11") (pinfunction "GND_11") (pintype "power_in"))
      (node (ref "IC2") (pin "4") (pinfunction "V-_4") (pintype "power_in"))
      (node (ref "IC3") (pin "3") (pinfunction "GND_3") (pintype "power_in"))
      (node (ref "IC4") (pin "11") (pinfunction "GND_11") (pintype "power_in"))
      (node (ref "IC5") (pin "11") (pinfunction "GND_11") (pintype "power_in"))
      (node (ref "IC6") (pin "3") (pinfunction "GND_3") (pintype "bidirectional"))
      (node (ref "IC7") (pin "4") (pinfunction "V-_4") (pintype "power_in"))
      (node (ref "IC8") (pin "11") (pinfunction "GND_11") (pintype "power_in"))
      (node (ref "IC9") (pin "4") (pinfunction "V-_4") (pintype "power_in"))
      (node (ref "JP1") (pin "12") (pinfunction "12_12") (pintype "passive"))
      (node (ref "JP10") (pin "2") (pinfunction "2_2") (pintype "passive"))
      (node (ref "JP11") (pin "12") (pinfunction "12_12") (pintype "passive"))
      (node (ref "JP12") (pin "2") (pinfunction "2_2") (pintype "passive"))
      (node (ref "JP13") (pin "2") (pinfunction "2_2") (pintype "passive"))
      (node (ref "JP2") (pin "12") (pinfunction "12_12") (pintype "passive"))
      (node (ref "JP3") (pin "2") (pinfunction "2_2") (pintype "passive"))
      (node (ref "JP4") (pin "1") (pinfunction "1_1") (pintype "passive"))
      (node (ref "JP5") (pin "2") (pinfunction "2_2") (pintype "passive"))
      (node (ref "JP6") (pin "2") (pinfunction "2_2") (pintype "passive"))
      (node (ref "JP7") (pin "2") (pinfunction "2_2") (pintype "passive"))
      (node (ref "JP8") (pin "12") (pinfunction "12_12") (pintype "passive"))
      (node (ref "JP9") (pin "2") (pinfunction "2_2") (pintype "passive"))
      (node (ref "L3") (pin "1") (pinfunction "P$1_1") (pintype "passive"))
      (node (ref "R1") (pin "1") (pinfunction "P$1_1") (pintype "passive"))
      (node (ref "R21") (pin "P$1") (pinfunction "1_P$1") (pintype "passive"))
      (node (ref "R23") (pin "P$1") (pinfunction "1_P$1") (pintype "passive"))
      (node (ref "R25") (pin "P$1") (pinfunction "1_P$1") (pintype "passive"))
      (node (ref "R27") (pin "P$1") (pinfunction "1_P$1") (pintype "passive"))
      (node (ref "R3") (pin "1") (pinfunction "P$1_1") (pintype "passive"))
      (node (ref "R37") (pin "1") (pinfunction "P$1_1") (pintype "passive"))
      (node (ref "R39") (pin "1") (pinfunction "P$1_1") (pintype "passive"))
      (node (ref "R41") (pin "P$2") (pinfunction "2_P$2") (pintype "passive"))
      (node (ref "R41") (pin "P$3") (pinfunction "3_P$3") (pintype "passive"))
      (node (ref "R42") (pin "P$2") (pinfunction "2_P$2") (pintype "passive"))
      (node (ref "R42") (pin "P$3") (pinfunction "3_P$3") (pintype "passive"))
      (node (ref "R55") (pin "1") (pinfunction "P$1_1") (pintype "passive"))
      (node (ref "R57") (pin "1") (pinfunction "P$1_1") (pintype "passive"))
      (node (ref "R59") (pin "P$2") (pinfunction "2_P$2") (pintype "passive"))
      (node (ref "R59") (pin "P$3") (pinfunction "3_P$3") (pintype "passive"))
      (node (ref "R6") (pin "P$2") (pinfunction "2_P$2") (pintype "passive"))
      (node (ref "R6") (pin "P$3") (pinfunction "3_P$3") (pintype "passive"))
      (node (ref "R60") (pin "P$2") (pinfunction "2_P$2") (pintype "passive"))
      (node (ref "R60") (pin "P$3") (pinfunction "3_P$3") (pintype "passive"))
      (node (ref "R7") (pin "P$2") (pinfunction "2_P$2") (pintype "passive"))
      (node (ref "R7") (pin "P$3") (pinfunction "3_P$3") (pintype "passive"))
      (node (ref "R73") (pin "1") (pinfunction "P$1_1") (pintype "passive"))
      (node (ref "R75") (pin "1") (pinfunction "P$1_1") (pintype "passive"))
      (node (ref "R77") (pin "P$2") (pinfunction "2_P$2") (pintype "passive"))
      (node (ref "R77") (pin "P$3") (pinfunction "3_P$3") (pintype "passive"))
      (node (ref "R78") (pin "P$2") (pinfunction "2_P$2") (pintype "passive"))
      (node (ref "R78") (pin "P$3") (pinfunction "3_P$3") (pintype "passive"))
      (node (ref "S1") (pin "P$2") (pinfunction "2_P$2") (pintype "bidirectional"))
      (node (ref "S1") (pin "P$5") (pinfunction "5_P$5") (pintype "bidirectional"))
      (node (ref "S2") (pin "P$2") (pinfunction "2_P$2") (pintype "bidirectional"))
      (node (ref "S2") (pin "P$5") (pinfunction "5_P$5") (pintype "bidirectional"))
      (node (ref "S3") (pin "P$2") (pinfunction "2_P$2") (pintype "bidirectional"))
      (node (ref "S3") (pin "P$5") (pinfunction "5_P$5") (pintype "bidirectional"))
      (node (ref "S4") (pin "P$2") (pinfunction "2_P$2") (pintype "bidirectional"))
      (node (ref "S4") (pin "P$5") (pinfunction "5_P$5") (pintype "bidirectional"))
      (node (ref "T1") (pin "2") (pinfunction "E_2") (pintype "passive"))
      (node (ref "T2") (pin "2") (pinfunction "E_2") (pintype "passive"))
      (node (ref "T3") (pin "2") (pinfunction "E_2") (pintype "passive"))
      (node (ref "T4") (pin "2") (pinfunction "E_2") (pintype "passive"))
      (node (ref "T5") (pin "2") (pinfunction "E_2") (pintype "passive"))
      (node (ref "T6") (pin "2") (pinfunction "E_2") (pintype "passive"))
      (node (ref "T7") (pin "2") (pinfunction "E_2") (pintype "passive"))
      (node (ref "T8") (pin "2") (pinfunction "E_2") (pintype "passive"))
      (node (ref "TP27") (pin "P$1") (pinfunction "P$1_P$1") (pintype "bidirectional"))
      (node (ref "U$1") (pin "AGND") (pinfunction "AGND_AGND") (pintype "power_in"))
      (node (ref "X1") (pin "2") (pinfunction "2_2") (pintype "passive"))
      (node (ref "X2") (pin "2") (pinfunction "2_2") (pintype "passive"))
      (node (ref "X3") (pin "2") (pinfunction "2_2") (pintype "passive"))
      (node (ref "X4") (pin "2") (pinfunction "2_2") (pintype "passive"))
      (node (ref "X5") (pin "2") (pinfunction "2_2") (pintype "passive"))
      (node (ref "X6") (pin "2") (pinfunction "2_2") (pintype "passive"))
      (node (ref "X7") (pin "2") (pinfunction "2_2") (pintype "passive"))
      (node (ref "X8") (pin "2") (pinfunction "2_2") (pintype "passive"))
    )
    (net (code "12") (name "CS_DAC") (class "Default")
      (node (ref "IC3") (pin "6") (pinfunction "SYNC_6") (pintype "bidirectional"))
      (node (ref "U$1") (pin "6") (pinfunction "6/PWM_6") (pintype "bidirectional"))
    )
    (net (code "13") (name "CS_LCD") (class "Default")
      (node (ref "LCD_HEADER") (pin "6") (pinfunction "6_6") (pintype "passive"))
      (node (ref "U$1") (pin "12") (pinfunction "12/MISO_12") (pintype "bidirectional"))
    )
    (net (code "14") (name "CS_POT1") (class "Default")
      (node (ref "IC4") (pin "9") (pinfunction "CS_9") (pintype "bidirectional"))
      (node (ref "U$1") (pin "2") (pinfunction "2_2") (pintype "bidirectional"))
    )
    (net (code "15") (name "CS_POT2") (class "Default")
      (node (ref "IC5") (pin "9") (pinfunction "CS_9") (pintype "bidirectional"))
      (node (ref "U$1") (pin "3") (pinfunction "3/CAN-TX/PWM_3") (pintype "bidirectional"))
    )
    (net (code "16") (name "CS_POT3") (class "Default")
      (node (ref "IC8") (pin "9") (pinfunction "CS_9") (pintype "bidirectional"))
      (node (ref "U$1") (pin "4") (pinfunction "4/CAN-RX-PWM_4") (pintype "bidirectional"))
    )
    (net (code "17") (name "CS_POT4") (class "Default")
      (node (ref "IC10") (pin "9") (pinfunction "CS_9") (pintype "bidirectional"))
      (node (ref "U$1") (pin "5") (pinfunction "5/PWM_5") (pintype "bidirectional"))
    )
    (net (code "18") (name "ENC_A1") (class "Default")
      (node (ref "C17") (pin "2") (pinfunction "2_2") (pintype "passive"))
      (node (ref "ENC1") (pin "A") (pinfunction "A_A") (pintype "bidirectional"))
      (node (ref "R28") (pin "P$1") (pinfunction "1_P$1") (pintype "passive"))
      (node (ref "U$1") (pin "17/A3") (pinfunction "17/A3/T_17/A3") (pintype "bidirectional"))
    )
    (net (code "19") (name "ENC_A2") (class "Default")
      (node (ref "C19") (pin "2") (pinfunction "2_2") (pintype "passive"))
      (node (ref "ENC2") (pin "A") (pinfunction "A_A") (pintype "bidirectional"))
      (node (ref "R33") (pin "P$1") (pinfunction "1_P$1") (pintype "passive"))
      (node (ref "U$1") (pin "14/A0") (pinfunction "14/A0_14/A0") (pintype "bidirectional"))
    )
    (net (code "20") (name "ENC_B1") (class "Default")
      (node (ref "C16") (pin "2") (pinfunction "2_2") (pintype "passive"))
      (node (ref "ENC1") (pin "B") (pinfunction "B_B") (pintype "bidirectional"))
      (node (ref "R19") (pin "1") (pinfunction "P$1_1") (pintype "passive"))
      (node (ref "U$1") (pin "7") (pinfunction "7/RX3_7") (pintype "bidirectional"))
    )
    (net (code "21") (name "ENC_B2") (class "Default")
      (node (ref "C18") (pin "2") (pinfunction "2_2") (pintype "passive"))
      (node (ref "ENC2") (pin "B") (pinfunction "B_B") (pintype "bidirectional"))
      (node (ref "R32") (pin "1") (pinfunction "P$1_1") (pintype "passive"))
      (node (ref "U$1") (pin "16/A2") (pinfunction "16/A2/T_16/A2") (pintype "bidirectional"))
    )
    (net (code "22") (name "ENC_SW1") (class "Default")
      (node (ref "ENC1") (pin "E") (pinfunction "E_E") (pintype "bidirectional"))
      (node (ref "R29") (pin "1") (pinfunction "P$1_1") (pintype "passive"))
      (node (ref "U$1") (pin "8") (pinfunction "8/TX3_8") (pintype "bidirectional"))
    )
    (net (code "23") (name "ENC_SW2") (class "Default")
      (node (ref "ENC2") (pin "E") (pinfunction "E_E") (pintype "bidirectional"))
      (node (ref "R34") (pin "1") (pinfunction "P$1_1") (pintype "passive"))
      (node (ref "U$1") (pin "15/A1") (pinfunction "15/A1/T_15/A1") (pintype "bidirectional"))
    )
    (net (code "24") (name "GND") (class "Default")
      (node (ref "C1") (pin "1") (pinfunction "P$1_1") (pintype "passive"))
      (node (ref "C16") (pin "1") (pinfunction "1_1") (pintype "passive"))
      (node (ref "C17") (pin "1") (pinfunction "1_1") (pintype "passive"))
      (node (ref "C18") (pin "1") (pinfunction "1_1") (pintype "passive"))
      (node (ref "C19") (pin "1") (pinfunction "1_1") (pintype "passive"))
      (node (ref "C2") (pin "1") (pinfunction "P$1_1") (pintype "passive"))
      (node (ref "IC10") (pin "12") (pinfunction "VSS_12") (pintype "power_in"))
      (node (ref "IC4") (pin "12") (pinfunction "VSS_12") (pintype "power_in"))
      (node (ref "IC5") (pin "12") (pinfunction "VSS_12") (pintype "power_in"))
      (node (ref "IC8") (pin "12") (pinfunction "VSS_12") (pintype "power_in"))
      (node (ref "L3") (pin "2") (pinfunction "P$2_2") (pintype "passive"))
      (node (ref "LCD_HEADER") (pin "2") (pinfunction "2_2") (pintype "passive"))
      (node (ref "LCD_HEADER") (pin "4") (pinfunction "4_4") (pintype "passive"))
      (node (ref "R30") (pin "1") (pinfunction "P$1_1") (pintype "passive"))
      (node (ref "R31") (pin "1") (pinfunction "P$1_1") (pintype "passive"))
      (node (ref "R35") (pin "1") (pinfunction "P$1_1") (pintype "passive"))
      (node (ref "R36") (pin "1") (pinfunction "P$1_1") (pintype "passive"))
      (node (ref "U$1") (pin "GND") (pinfunction "GND_GND") (pintype "power_in"))
      (node (ref "U$1") (pin "GND1") (pinfunction "GND_GND1") (pintype "power_in"))
    )
    (net (code "25") (name "I1") (class "Default")
      (node (ref "IC4") (pin "16") (pinfunction "A2_16") (pintype "bidirectional"))
      (node (ref "JP1") (pin "5") (pinfunction "5_5") (pintype "passive"))
      (node (ref "TP6") (pin "P$1") (pinfunction "P$1_P$1") (pintype "bidirectional"))
    )
    (net (code "26") (name "I2") (class "Default")
      (node (ref "IC5") (pin "16") (pinfunction "A2_16") (pintype "bidirectional"))
      (node (ref "JP2") (pin "5") (pinfunction "5_5") (pintype "passive"))
      (node (ref "TP13") (pin "P$1") (pinfunction "P$1_P$1") (pintype "bidirectional"))
    )
    (net (code "27") (name "I3") (class "Default")
      (node (ref "IC8") (pin "16") (pinfunction "A2_16") (pintype "bidirectional"))
      (node (ref "JP8") (pin "5") (pinfunction "5_5") (pintype "passive"))
      (node (ref "TP19") (pin "P$1") (pinfunction "P$1_P$1") (pintype "bidirectional"))
    )
    (net (code "28") (name "I4") (class "Default")
      (node (ref "IC10") (pin "16") (pinfunction "A2_16") (pintype "bidirectional"))
      (node (ref "JP11") (pin "5") (pinfunction "5_5") (pintype "passive"))
      (node (ref "TP25") (pin "P$1") (pinfunction "P$1_P$1") (pintype "bidirectional"))
    )
    (net (code "29") (name "LIMA1") (class "Default")
      (node (ref "JP1") (pin "4") (pinfunction "4_4") (pintype "passive"))
      (node (ref "R2") (pin "2") (pinfunction "P$2_2") (pintype "passive"))
      (node (ref "T1") (pin "3") (pinfunction "C_3") (pintype "passive"))
    )
    (net (code "30") (name "LIMA2") (class "Default")
      (node (ref "JP2") (pin "4") (pinfunction "4_4") (pintype "passive"))
      (node (ref "R38") (pin "2") (pinfunction "P$2_2") (pintype "passive"))
      (node (ref "T3") (pin "3") (pinfunction "C_3") (pintype "passive"))
    )
    (net (code "31") (name "LIMA3") (class "Default")
      (node (ref "JP8") (pin "4") (pinfunction "4_4") (pintype "passive"))
      (node (ref "R56") (pin "2") (pinfunction "P$2_2") (pintype "passive"))
      (node (ref "T5") (pin "3") (pinfunction "C_3") (pintype "passive"))
    )
    (net (code "32") (name "LIMA4") (class "Default")
      (node (ref "JP11") (pin "4") (pinfunction "4_4") (pintype "passive"))
      (node (ref "R74") (pin "2") (pinfunction "P$2_2") (pintype "passive"))
      (node (ref "T7") (pin "3") (pinfunction "C_3") (pintype "passive"))
    )
    (net (code "33") (name "LIMB1") (class "Default")
      (node (ref "JP1") (pin "6") (pinfunction "6_6") (pintype "passive"))
      (node (ref "R4") (pin "2") (pinfunction "P$2_2") (pintype "passive"))
      (node (ref "T2") (pin "3") (pinfunction "C_3") (pintype "passive"))
    )
    (net (code "34") (name "LIMB2") (class "Default")
      (node (ref "JP2") (pin "6") (pinfunction "6_6") (pintype "passive"))
      (node (ref "R40") (pin "2") (pinfunction "P$2_2") (pintype "passive"))
      (node (ref "T4") (pin "3") (pinfunction "C_3") (pintype "passive"))
    )
    (net (code "35") (name "LIMB3") (class "Default")
      (node (ref "JP8") (pin "6") (pinfunction "6_6") (pintype "passive"))
      (node (ref "R58") (pin "2") (pinfunction "P$2_2") (pintype "passive"))
      (node (ref "T6") (pin "3") (pinfunction "C_3") (pintype "passive"))
    )
    (net (code "36") (name "LIMB4") (class "Default")
      (node (ref "JP11") (pin "6") (pinfunction "6_6") (pintype "passive"))
      (node (ref "R76") (pin "2") (pinfunction "P$2_2") (pintype "passive"))
      (node (ref "T8") (pin "3") (pinfunction "C_3") (pintype "passive"))
    )
    (net (code "37") (name "MOSI") (class "Default")
      (node (ref "LCD_HEADER") (pin "3") (pinfunction "3_3") (pintype "passive"))
      (node (ref "U$1") (pin "11") (pinfunction "11/MOSI_11") (pintype "bidirectional"))
    )
    (net (code "38") (name "MOSI_B") (class "Default")
      (node (ref "IC10") (pin "8") (pinfunction "SDI_8") (pintype "bidirectional"))
      (node (ref "IC3") (pin "8") (pinfunction "DIN_8") (pintype "bidirectional"))
      (node (ref "IC4") (pin "8") (pinfunction "SDI_8") (pintype "bidirectional"))
      (node (ref "IC5") (pin "8") (pinfunction "SDI_8") (pintype "bidirectional"))
      (node (ref "IC8") (pin "8") (pinfunction "SDI_8") (pintype "bidirectional"))
      (node (ref "U$1") (pin "0") (pinfunction "0/RX1/T_0") (pintype "bidirectional"))
    )
    (net (code "39") (name "Net-(C1-P$2)") (class "Default")
      (node (ref "C1") (pin "2") (pinfunction "P$2_2") (pintype "passive"))
      (node (ref "C2") (pin "2") (pinfunction "P$2_2") (pintype "passive"))
      (node (ref "L2") (pin "1") (pinfunction "P$1_1") (pintype "passive"))
      (node (ref "U$1") (pin "VIN") (pinfunction "VIN_VIN") (pintype "power_in"))
    )
    (net (code "40") (name "Net-(C26-P$1)") (class "Default")
      (node (ref "C26") (pin "1") (pinfunction "P$1_1") (pintype "passive"))
      (node (ref "JP14") (pin "1") (pinfunction "1_1") (pintype "passive"))
    )
    (net (code "41") (name "Net-(C27-P$2)") (class "Default")
      (node (ref "C27") (pin "2") (pinfunction "P$2_2") (pintype "passive"))
      (node (ref "C30") (pin "2") (pinfunction "P$2_2") (pintype "passive"))
      (node (ref "IC3") (pin "9") (pinfunction "VDD_9") (pintype "power_in"))
      (node (ref "L1") (pin "1") (pinfunction "P$1_1") (pintype "passive"))
    )
    (net (code "42") (name "Net-(ENC1-GND)") (class "Default")
      (node (ref "ENC1") (pin "C") (pinfunction "GND_C") (pintype "bidirectional"))
      (node (ref "R30") (pin "2") (pinfunction "P$2_2") (pintype "passive"))
    )
    (net (code "43") (name "Net-(ENC2-GND)") (class "Default")
      (node (ref "ENC2") (pin "C") (pinfunction "GND_C") (pintype "bidirectional"))
      (node (ref "R35") (pin "2") (pinfunction "P$2_2") (pintype "passive"))
    )
    (net (code "44") (name "Net-(IC1A--IN)") (class "Default")
      (node (ref "IC1") (pin "2") (pinfunction "-IN_2") (pintype "input"))
      (node (ref "R6") (pin "P$1") (pinfunction "1_P$1") (pintype "passive"))
      (node (ref "R8") (pin "1") (pinfunction "P$1_1") (pintype "passive"))
      (node (ref "TP2") (pin "P$1") (pinfunction "P$1_P$1") (pintype "bidirectional"))
    )
    (net (code "45") (name "Net-(IC1A-OUT)") (class "Default")
      (node (ref "IC1") (pin "1") (pinfunction "OUT_1") (pintype "output"))
      (node (ref "R10") (pin "2") (pinfunction "P$2_2") (pintype "passive"))
      (node (ref "R9") (pin "1") (pinfunction "P$1_1") (pintype "passive"))
    )
    (net (code "46") (name "Net-(IC1B-+IN)") (class "Default")
      (node (ref "IC1") (pin "5") (pinfunction "+IN_5") (pintype "input"))
      (node (ref "R11") (pin "1") (pinfunction "P$1_1") (pintype "passive"))
      (node (ref "R7") (pin "P$1") (pinfunction "1_P$1") (pintype "passive"))
      (node (ref "TP3") (pin "P$1") (pinfunction "P$1_P$1") (pintype "bidirectional"))
    )
    (net (code "47") (name "Net-(IC1B-OUT)") (class "Default")
      (node (ref "IC1") (pin "7") (pinfunction "OUT_7") (pintype "output"))
      (node (ref "R12") (pin "1") (pinfunction "P$1_1") (pintype "passive"))
      (node (ref "R13") (pin "2") (pinfunction "P$2_2") (pintype "passive"))
    )
    (net (code "48") (name "Net-(IC2A--IN)") (class "Default")
      (node (ref "IC2") (pin "2") (pinfunction "-IN_2") (pintype "input"))
      (node (ref "R41") (pin "P$1") (pinfunction "1_P$1") (pintype "passive"))
      (node (ref "R43") (pin "1") (pinfunction "P$1_1") (pintype "passive"))
      (node (ref "TP9") (pin "P$1") (pinfunction "P$1_P$1") (pintype "bidirectional"))
    )
    (net (code "49") (name "Net-(IC2A-OUT)") (class "Default")
      (node (ref "IC2") (pin "1") (pinfunction "OUT_1") (pintype "output"))
      (node (ref "R44") (pin "1") (pinfunction "P$1_1") (pintype "passive"))
      (node (ref "R45") (pin "2") (pinfunction "P$2_2") (pintype "passive"))
    )
    (net (code "50") (name "Net-(IC2B-+IN)") (class "Default")
      (node (ref "IC2") (pin "5") (pinfunction "+IN_5") (pintype "input"))
      (node (ref "R42") (pin "P$1") (pinfunction "1_P$1") (pintype "passive"))
      (node (ref "R46") (pin "1") (pinfunction "P$1_1") (pintype "passive"))
      (node (ref "TP10") (pin "P$1") (pinfunction "P$1_P$1") (pintype "bidirectional"))
    )
    (net (code "51") (name "Net-(IC2B-OUT)") (class "Default")
      (node (ref "IC2") (pin "7") (pinfunction "OUT_7") (pintype "output"))
      (node (ref "R47") (pin "1") (pinfunction "P$1_1") (pintype "passive"))
      (node (ref "R48") (pin "2") (pinfunction "P$2_2") (pintype "passive"))
    )
    (net (code "52") (name "Net-(IC3-VREF)") (class "Default")
      (node (ref "IC3") (pin "10") (pinfunction "VREF_10") (pintype "bidirectional"))
      (node (ref "JP14") (pin "3") (pinfunction "3_3") (pintype "passive"))
      (node (ref "JP14") (pin "4") (pinfunction "4_4") (pintype "passive"))
      (node (ref "TP1") (pin "P$1") (pinfunction "P$1_P$1") (pintype "bidirectional"))
    )
    (net (code "53") (name "Net-(IC7A--IN)") (class "Default")
      (node (ref "IC7") (pin "2") (pinfunction "-IN_2") (pintype "input"))
      (node (ref "R59") (pin "P$1") (pinfunction "1_P$1") (pintype "passive"))
      (node (ref "R61") (pin "1") (pinfunction "P$1_1") (pintype "passive"))
      (node (ref "TP15") (pin "P$1") (pinfunction "P$1_P$1") (pintype "bidirectional"))
    )
    (net (code "54") (name "Net-(IC7A-OUT)") (class "Default")
      (node (ref "IC7") (pin "1") (pinfunction "OUT_1") (pintype "output"))
      (node (ref "R62") (pin "1") (pinfunction "P$1_1") (pintype "passive"))
      (node (ref "R63") (pin "2") (pinfunction "P$2_2") (pintype "passive"))
    )
    (net (code "55") (name "Net-(IC7B-+IN)") (class "Default")
      (node (ref "IC7") (pin "5") (pinfunction "+IN_5") (pintype "input"))
      (node (ref "R60") (pin "P$1") (pinfunction "1_P$1") (pintype "passive"))
      (node (ref "R64") (pin "1") (pinfunction "P$1_1") (pintype "passive"))
      (node (ref "TP16") (pin "P$1") (pinfunction "P$1_P$1") (pintype "bidirectional"))
    )
    (net (code "56") (name "Net-(IC7B-OUT)") (class "Default")
      (node (ref "IC7") (pin "7") (pinfunction "OUT_7") (pintype "output"))
      (node (ref "R65") (pin "1") (pinfunction "P$1_1") (pintype "passive"))
      (node (ref "R66") (pin "2") (pinfunction "P$2_2") (pintype "passive"))
    )
    (net (code "57") (name "Net-(IC9A--IN)") (class "Default")
      (node (ref "IC9") (pin "2") (pinfunction "-IN_2") (pintype "input"))
      (node (ref "R77") (pin "P$1") (pinfunction "1_P$1") (pintype "passive"))
      (node (ref "R79") (pin "1") (pinfunction "P$1_1") (pintype "passive"))
      (node (ref "TP21") (pin "P$1") (pinfunction "P$1_P$1") (pintype "bidirectional"))
    )
    (net (code "58") (name "Net-(IC9A-OUT)") (class "Default")
      (node (ref "IC9") (pin "1") (pinfunction "OUT_1") (pintype "output"))
      (node (ref "R80") (pin "1") (pinfunction "P$1_1") (pintype "passive"))
      (node (ref "R81") (pin "2") (pinfunction "P$2_2") (pintype "passive"))
    )
    (net (code "59") (name "Net-(IC9B-+IN)") (class "Default")
      (node (ref "IC9") (pin "5") (pinfunction "+IN_5") (pintype "input"))
      (node (ref "R78") (pin "P$1") (pinfunction "1_P$1") (pintype "passive"))
      (node (ref "R82") (pin "1") (pinfunction "P$1_1") (pintype "passive"))
      (node (ref "TP22") (pin "P$1") (pinfunction "P$1_P$1") (pintype "bidirectional"))
    )
    (net (code "60") (name "Net-(IC9B-OUT)") (class "Default")
      (node (ref "IC9") (pin "7") (pinfunction "OUT_7") (pintype "output"))
      (node (ref "R83") (pin "1") (pinfunction "P$1_1") (pintype "passive"))
      (node (ref "R84") (pin "2") (pinfunction "P$2_2") (pintype "passive"))
    )
    (net (code "61") (name "Net-(LCD_HEADER-Pad1)") (class "Default")
      (node (ref "LCD_HEADER") (pin "1") (pinfunction "1_1") (pintype "passive"))
      (node (ref "U$1") (pin "3.3V") (pinfunction "3.3V_3.3V") (pintype "power_in"))
      (node (ref "U$1") (pin "3.3V1") (pinfunction "3.3V_3.3V1") (pintype "power_in"))
    )
    (net (code "62") (name "Net-(R1-P$2)") (class "Default")
      (node (ref "JP3") (pin "1") (pinfunction "1_1") (pintype "passive"))
      (node (ref "R1") (pin "2") (pinfunction "P$2_2") (pintype "passive"))
      (node (ref "R2") (pin "1") (pinfunction "P$1_1") (pintype "passive"))
      (node (ref "S1") (pin "P$3") (pinfunction "3_P$3") (pintype "bidirectional"))
    )
    (net (code "63") (name "Net-(R3-P$2)") (class "Default")
      (node (ref "JP5") (pin "1") (pinfunction "1_1") (pintype "passive"))
      (node (ref "R3") (pin "2") (pinfunction "P$2_2") (pintype "passive"))
      (node (ref "R4") (pin "1") (pinfunction "P$1_1") (pintype "passive"))
      (node (ref "S1") (pin "P$6") (pinfunction "6_P$6") (pintype "bidirectional"))
    )
    (net (code "64") (name "Net-(R5-P$1)") (class "Default")
      (node (ref "R5") (pin "1") (pinfunction "P$1_1") (pintype "passive"))
      (node (ref "S1") (pin "P$4") (pinfunction "4_P$4") (pintype "bidirectional"))
    )
    (net (code "65") (name "Net-(R5-P$2)") (class "Default")
      (node (ref "D1") (pin "C") (pinfunction "C_C") (pintype "bidirectional"))
      (node (ref "R5") (pin "2") (pinfunction "P$2_2") (pintype "passive"))
    )
    (net (code "66") (name "Net-(R10-P$1)") (class "Default")
      (node (ref "R10") (pin "1") (pinfunction "P$1_1") (pintype "passive"))
      (node (ref "T1") (pin "1") (pinfunction "B_1") (pintype "passive"))
    )
    (net (code "67") (name "Net-(R13-P$1)") (class "Default")
      (node (ref "R13") (pin "1") (pinfunction "P$1_1") (pintype "passive"))
      (node (ref "T2") (pin "1") (pinfunction "B_1") (pintype "passive"))
    )
    (net (code "68") (name "Net-(R14-P$1)") (class "Default")
      (node (ref "JP1") (pin "8") (pinfunction "8_8") (pintype "passive"))
      (node (ref "R14") (pin "1") (pinfunction "P$1_1") (pintype "passive"))
      (node (ref "R15") (pin "1") (pinfunction "P$1_1") (pintype "passive"))
    )
    (net (code "69") (name "Net-(R14-P$2)") (class "Default")
      (node (ref "R14") (pin "2") (pinfunction "P$2_2") (pintype "passive"))
      (node (ref "X1") (pin "1") (pinfunction "1_1") (pintype "passive"))
    )
    (net (code "70") (name "Net-(R18-P$2)") (class "Default")
      (node (ref "R18") (pin "2") (pinfunction "P$2_2") (pintype "passive"))
      (node (ref "X2") (pin "1") (pinfunction "1_1") (pintype "passive"))
    )
    (net (code "71") (name "Net-(R31-P$2)") (class "Default")
      (node (ref "ENC1") (pin "D") (pinfunction "D_D") (pintype "bidirectional"))
      (node (ref "R31") (pin "2") (pinfunction "P$2_2") (pintype "passive"))
    )
    (net (code "72") (name "Net-(R36-P$2)") (class "Default")
      (node (ref "ENC2") (pin "D") (pinfunction "D_D") (pintype "bidirectional"))
      (node (ref "R36") (pin "2") (pinfunction "P$2_2") (pintype "passive"))
    )
    (net (code "73") (name "Net-(R37-P$2)") (class "Default")
      (node (ref "JP6") (pin "1") (pinfunction "1_1") (pintype "passive"))
      (node (ref "R37") (pin "2") (pinfunction "P$2_2") (pintype "passive"))
      (node (ref "R38") (pin "1") (pinfunction "P$1_1") (pintype "passive"))
      (node (ref "S2") (pin "P$3") (pinfunction "3_P$3") (pintype "bidirectional"))
    )
    (net (code "74") (name "Net-(R39-P$2)") (class "Default")
      (node (ref "JP7") (pin "1") (pinfunction "1_1") (pintype "passive"))
      (node (ref "R39") (pin "2") (pinfunction "P$2_2") (pintype "passive"))
      (node (ref "R40") (pin "1") (pinfunction "P$1_1") (pintype "passive"))
      (node (ref "S2") (pin "P$6") (pinfunction "6_P$6") (pintype "bidirectional"))
    )
    (net (code "75") (name "Net-(R45-P$1)") (class "Default")
      (node (ref "R45") (pin "1") (pinfunction "P$1_1") (pintype "passive"))
      (node (ref "T3") (pin "1") (pinfunction "B_1") (pintype "passive"))
    )
    (net (code "76") (name "Net-(R48-P$1)") (class "Default")
      (node (ref "R48") (pin "1") (pinfunction "P$1_1") (pintype "passive"))
      (node (ref "T4") (pin "1") (pinfunction "B_1") (pintype "passive"))
    )
    (net (code "77") (name "Net-(R49-P$1)") (class "Default")
      (node (ref "R49") (pin "1") (pinfunction "P$1_1") (pintype "passive"))
      (node (ref "S2") (pin "P$4") (pinfunction "4_P$4") (pintype "bidirectional"))
    )
    (net (code "78") (name "Net-(R49-P$2)") (class "Default")
      (node (ref "D2") (pin "C") (pinfunction "C_C") (pintype "bidirectional"))
      (node (ref "R49") (pin "2") (pinfunction "P$2_2") (pintype "passive"))
    )
    (net (code "79") (name "Net-(R52-P$1)") (class "Default")
      (node (ref "JP2") (pin "8") (pinfunction "8_8") (pintype "passive"))
      (node (ref "R52") (pin "1") (pinfunction "P$1_1") (pintype "passive"))
      (node (ref "R53") (pin "1") (pinfunction "P$1_1") (pintype "passive"))
    )
    (net (code "80") (name "Net-(R52-P$2)") (class "Default")
      (node (ref "R52") (pin "2") (pinfunction "P$2_2") (pintype "passive"))
      (node (ref "X3") (pin "1") (pinfunction "1_1") (pintype "passive"))
    )
    (net (code "81") (name "Net-(R54-P$2)") (class "Default")
      (node (ref "R54") (pin "2") (pinfunction "P$2_2") (pintype "passive"))
      (node (ref "X4") (pin "1") (pinfunction "1_1") (pintype "passive"))
    )
    (net (code "82") (name "Net-(R55-P$2)") (class "Default")
      (node (ref "JP9") (pin "1") (pinfunction "1_1") (pintype "passive"))
      (node (ref "R55") (pin "2") (pinfunction "P$2_2") (pintype "passive"))
      (node (ref "R56") (pin "1") (pinfunction "P$1_1") (pintype "passive"))
      (node (ref "S3") (pin "P$3") (pinfunction "3_P$3") (pintype "bidirectional"))
    )
    (net (code "83") (name "Net-(R57-P$2)") (class "Default")
      (node (ref "JP10") (pin "1") (pinfunction "1_1") (pintype "passive"))
      (node (ref "R57") (pin "2") (pinfunction "P$2_2") (pintype "passive"))
      (node (ref "R58") (pin "1") (pinfunction "P$1_1") (pintype "passive"))
      (node (ref "S3") (pin "P$6") (pinfunction "6_P$6") (pintype "bidirectional"))
    )
    (net (code "84") (name "Net-(R63-P$1)") (class "Default")
      (node (ref "R63") (pin "1") (pinfunction "P$1_1") (pintype "passive"))
      (node (ref "T5") (pin "1") (pinfunction "B_1") (pintype "passive"))
    )
    (net (code "85") (name "Net-(R66-P$1)") (class "Default")
      (node (ref "R66") (pin "1") (pinfunction "P$1_1") (pintype "passive"))
      (node (ref "T6") (pin "1") (pinfunction "B_1") (pintype "passive"))
    )
    (net (code "86") (name "Net-(R67-P$1)") (class "Default")
      (node (ref "R67") (pin "1") (pinfunction "P$1_1") (pintype "passive"))
      (node (ref "S3") (pin "P$4") (pinfunction "4_P$4") (pintype "bidirectional"))
    )
    (net (code "87") (name "Net-(R67-P$2)") (class "Default")
      (node (ref "D3") (pin "C") (pinfunction "C_C") (pintype "bidirectional"))
      (node (ref "R67") (pin "2") (pinfunction "P$2_2") (pintype "passive"))
    )
    (net (code "88") (name "Net-(R70-P$1)") (class "Default")
      (node (ref "JP8") (pin "8") (pinfunction "8_8") (pintype "passive"))
      (node (ref "R70") (pin "1") (pinfunction "P$1_1") (pintype "passive"))
      (node (ref "R71") (pin "1") (pinfunction "P$1_1") (pintype "passive"))
    )
    (net (code "89") (name "Net-(R70-P$2)") (class "Default")
      (node (ref "R70") (pin "2") (pinfunction "P$2_2") (pintype "passive"))
      (node (ref "X5") (pin "1") (pinfunction "1_1") (pintype "passive"))
    )
    (net (code "90") (name "Net-(R72-P$2)") (class "Default")
      (node (ref "R72") (pin "2") (pinfunction "P$2_2") (pintype "passive"))
      (node (ref "X6") (pin "1") (pinfunction "1_1") (pintype "passive"))
    )
    (net (code "91") (name "Net-(R73-P$2)") (class "Default")
      (node (ref "JP12") (pin "1") (pinfunction "1_1") (pintype "passive"))
      (node (ref "R73") (pin "2") (pinfunction "P$2_2") (pintype "passive"))
      (node (ref "R74") (pin "1") (pinfunction "P$1_1") (pintype "passive"))
      (node (ref "S4") (pin "P$3") (pinfunction "3_P$3") (pintype "bidirectional"))
    )
    (net (code "92") (name "Net-(R75-P$2)") (class "Default")
      (node (ref "JP13") (pin "1") (pinfunction "1_1") (pintype "passive"))
      (node (ref "R75") (pin "2") (pinfunction "P$2_2") (pintype "passive"))
      (node (ref "R76") (pin "1") (pinfunction "P$1_1") (pintype "passive"))
      (node (ref "S4") (pin "P$6") (pinfunction "6_P$6") (pintype "bidirectional"))
    )
    (net (code "93") (name "Net-(R81-P$1)") (class "Default")
      (node (ref "R81") (pin "1") (pinfunction "P$1_1") (pintype "passive"))
      (node (ref "T7") (pin "1") (pinfunction "B_1") (pintype "passive"))
    )
    (net (code "94") (name "Net-(R84-P$1)") (class "Default")
      (node (ref "R84") (pin "1") (pinfunction "P$1_1") (pintype "passive"))
      (node (ref "T8") (pin "1") (pinfunction "B_1") (pintype "passive"))
    )
    (net (code "95") (name "Net-(R85-P$1)") (class "Default")
      (node (ref "R85") (pin "1") (pinfunction "P$1_1") (pintype "passive"))
      (node (ref "S4") (pin "P$4") (pinfunction "4_P$4") (pintype "bidirectional"))
    )
    (net (code "96") (name "Net-(R85-P$2)") (class "Default")
      (node (ref "D4") (pin "C") (pinfunction "C_C") (pintype "bidirectional"))
      (node (ref "R85") (pin "2") (pinfunction "P$2_2") (pintype "passive"))
    )
    (net (code "97") (name "Net-(R88-P$1)") (class "Default")
      (node (ref "JP11") (pin "8") (pinfunction "8_8") (pintype "passive"))
      (node (ref "R88") (pin "1") (pinfunction "P$1_1") (pintype "passive"))
      (node (ref "R89") (pin "1") (pinfunction "P$1_1") (pintype "passive"))
    )
    (net (code "98") (name "Net-(R88-P$2)") (class "Default")
      (node (ref "R88") (pin "2") (pinfunction "P$2_2") (pintype "passive"))
      (node (ref "X7") (pin "1") (pinfunction "1_1") (pintype "passive"))
    )
    (net (code "99") (name "Net-(R90-P$2)") (class "Default")
      (node (ref "R90") (pin "2") (pinfunction "P$2_2") (pintype "passive"))
      (node (ref "X8") (pin "1") (pinfunction "1_1") (pintype "passive"))
    )
    (net (code "100") (name "P1") (class "Default")
      (node (ref "IC4") (pin "2") (pinfunction "A1_2") (pintype "bidirectional"))
      (node (ref "JP1") (pin "1") (pinfunction "1_1") (pintype "passive"))
      (node (ref "TP4") (pin "P$1") (pinfunction "P$1_P$1") (pintype "bidirectional"))
    )
    (net (code "101") (name "P2") (class "Default")
      (node (ref "IC5") (pin "2") (pinfunction "A1_2") (pintype "bidirectional"))
      (node (ref "JP2") (pin "1") (pinfunction "1_1") (pintype "passive"))
      (node (ref "TP11") (pin "P$1") (pinfunction "P$1_P$1") (pintype "bidirectional"))
    )
    (net (code "102") (name "P3") (class "Default")
      (node (ref "IC8") (pin "2") (pinfunction "A1_2") (pintype "bidirectional"))
      (node (ref "JP8") (pin "1") (pinfunction "1_1") (pintype "passive"))
      (node (ref "TP17") (pin "P$1") (pinfunction "P$1_P$1") (pintype "bidirectional"))
    )
    (net (code "103") (name "P4") (class "Default")
      (node (ref "IC10") (pin "2") (pinfunction "A1_2") (pintype "bidirectional"))
      (node (ref "JP11") (pin "1") (pinfunction "1_1") (pintype "passive"))
      (node (ref "TP23") (pin "P$1") (pinfunction "P$1_P$1") (pintype "bidirectional"))
    )
    (net (code "104") (name "RST_LCD") (class "Default")
      (node (ref "LCD_HEADER") (pin "8") (pinfunction "8_8") (pintype "passive"))
      (node (ref "U$1") (pin "9") (pinfunction "9/RX2/PWM_9") (pintype "bidirectional"))
    )
    (net (code "105") (name "RS_LCD") (class "Default")
      (node (ref "LCD_HEADER") (pin "7") (pinfunction "7_7") (pintype "passive"))
      (node (ref "U$1") (pin "10") (pinfunction "10/TX2/PWM_10") (pintype "bidirectional"))
    )
    (net (code "106") (name "SCK") (class "Default")
      (node (ref "LCD_HEADER") (pin "5") (pinfunction "5_5") (pintype "passive"))
      (node (ref "U$1") (pin "13") (pinfunction "13/SCK/LED_13") (pintype "bidirectional"))
    )
    (net (code "107") (name "SCK_B") (class "Default")
      (node (ref "IC10") (pin "7") (pinfunction "CLK_7") (pintype "bidirectional"))
      (node (ref "IC3") (pin "7") (pinfunction "SCLK_7") (pintype "bidirectional"))
      (node (ref "IC4") (pin "7") (pinfunction "CLK_7") (pintype "bidirectional"))
      (node (ref "IC5") (pin "7") (pinfunction "CLK_7") (pintype "bidirectional"))
      (node (ref "IC8") (pin "7") (pinfunction "CLK_7") (pintype "bidirectional"))
      (node (ref "U$1") (pin "1") (pinfunction "1/TX1/T_1") (pintype "bidirectional"))
    )
    (net (code "108") (name "VBAT") (class "Default")
      (node (ref "U$1") (pin "VBAT") (pinfunction "VBAT_VBAT") (pintype "power_in"))
    )
    (net (code "109") (name "VDD") (class "Default")
      (node (ref "C12") (pin "2") (pinfunction "P$2_2") (pintype "passive"))
      (node (ref "C13") (pin "2") (pinfunction "P$2_2") (pintype "passive"))
      (node (ref "C15") (pin "2") (pinfunction "P$2_2") (pintype "passive"))
      (node (ref "C20") (pin "2") (pinfunction "P$2_2") (pintype "passive"))
      (node (ref "C21") (pin "2") (pinfunction "P$2_2") (pintype "passive"))
      (node (ref "C22") (pin "2") (pinfunction "P$2_2") (pintype "passive"))
      (node (ref "C23") (pin "2") (pinfunction "P$2_2") (pintype "passive"))
      (node (ref "C24") (pin "2") (pinfunction "P$2_2") (pintype "passive"))
      (node (ref "C25") (pin "2") (pinfunction "P$2_2") (pintype "passive"))
      (node (ref "CP3") (pin "+") (pinfunction "+_+") (pintype "passive"))
      (node (ref "D1") (pin "A") (pinfunction "A_A") (pintype "bidirectional"))
      (node (ref "D2") (pin "A") (pinfunction "A_A") (pintype "bidirectional"))
      (node (ref "D3") (pin "A") (pinfunction "A_A") (pintype "bidirectional"))
      (node (ref "D4") (pin "A") (pinfunction "A_A") (pintype "bidirectional"))
      (node (ref "IC1") (pin "8") (pinfunction "V+_8") (pintype "power_in"))
      (node (ref "IC10") (pin "10") (pinfunction "PR_10") (pintype "bidirectional"))
      (node (ref "IC10") (pin "13") (pinfunction "VL_13") (pintype "power_in"))
      (node (ref "IC10") (pin "5") (pinfunction "VDD_5") (pintype "power_in"))
      (node (ref "IC10") (pin "6") (pinfunction "SHDN_6") (pintype "bidirectional"))
      (node (ref "IC2") (pin "8") (pinfunction "V+_8") (pintype "power_in"))
      (node (ref "IC4") (pin "10") (pinfunction "PR_10") (pintype "bidirectional"))
      (node (ref "IC4") (pin "13") (pinfunction "VL_13") (pintype "power_in"))
      (node (ref "IC4") (pin "5") (pinfunction "VDD_5") (pintype "power_in"))
      (node (ref "IC4") (pin "6") (pinfunction "SHDN_6") (pintype "bidirectional"))
      (node (ref "IC5") (pin "10") (pinfunction "PR_10") (pintype "bidirectional"))
      (node (ref "IC5") (pin "13") (pinfunction "VL_13") (pintype "power_in"))
      (node (ref "IC5") (pin "5") (pinfunction "VDD_5") (pintype "power_in"))
      (node (ref "IC5") (pin "6") (pinfunction "SHDN_6") (pintype "bidirectional"))
      (node (ref "IC6") (pin "1") (pinfunction "IN_1") (pintype "bidirectional"))
      (node (ref "IC7") (pin "8") (pinfunction "V+_8") (pintype "power_in"))
      (node (ref "IC8") (pin "10") (pinfunction "PR_10") (pintype "bidirectional"))
      (node (ref "IC8") (pin "13") (pinfunction "VL_13") (pintype "power_in"))
      (node (ref "IC8") (pin "5") (pinfunction "VDD_5") (pintype "power_in"))
      (node (ref "IC8") (pin "6") (pinfunction "SHDN_6") (pintype "bidirectional"))
      (node (ref "IC9") (pin "8") (pinfunction "V+_8") (pintype "power_in"))
      (node (ref "JP1") (pin "11") (pinfunction "11_11") (pintype "passive"))
      (node (ref "JP1") (pin "2") (pinfunction "2_2") (pintype "passive"))
      (node (ref "JP11") (pin "11") (pinfunction "11_11") (pintype "passive"))
      (node (ref "JP11") (pin "2") (pinfunction "2_2") (pintype "passive"))
      (node (ref "JP2") (pin "11") (pinfunction "11_11") (pintype "passive"))
      (node (ref "JP2") (pin "2") (pinfunction "2_2") (pintype "passive"))
      (node (ref "JP8") (pin "11") (pinfunction "11_11") (pintype "passive"))
      (node (ref "JP8") (pin "2") (pinfunction "2_2") (pintype "passive"))
      (node (ref "L1") (pin "2") (pinfunction "P$2_2") (pintype "passive"))
      (node (ref "L2") (pin "2") (pinfunction "P$2_2") (pintype "passive"))
      (node (ref "L4") (pin "1") (pinfunction "P$1_1") (pintype "passive"))
      (node (ref "R11") (pin "2") (pinfunction "P$2_2") (pintype "passive"))
      (node (ref "R12") (pin "2") (pinfunction "P$2_2") (pintype "passive"))
      (node (ref "R19") (pin "2") (pinfunction "P$2_2") (pintype "passive"))
      (node (ref "R28") (pin "P$2") (pinfunction "2_P$2") (pintype "passive"))
      (node (ref "R29") (pin "2") (pinfunction "P$2_2") (pintype "passive"))
      (node (ref "R32") (pin "2") (pinfunction "P$2_2") (pintype "passive"))
      (node (ref "R33") (pin "P$2") (pinfunction "2_P$2") (pintype "passive"))
      (node (ref "R34") (pin "2") (pinfunction "P$2_2") (pintype "passive"))
      (node (ref "R43") (pin "2") (pinfunction "P$2_2") (pintype "passive"))
      (node (ref "R44") (pin "2") (pinfunction "P$2_2") (pintype "passive"))
      (node (ref "R46") (pin "2") (pinfunction "P$2_2") (pintype "passive"))
      (node (ref "R47") (pin "2") (pinfunction "P$2_2") (pintype "passive"))
      (node (ref "R61") (pin "2") (pinfunction "P$2_2") (pintype "passive"))
      (node (ref "R62") (pin "2") (pinfunction "P$2_2") (pintype "passive"))
      (node (ref "R64") (pin "2") (pinfunction "P$2_2") (pintype "passive"))
      (node (ref "R65") (pin "2") (pinfunction "P$2_2") (pintype "passive"))
      (node (ref "R79") (pin "2") (pinfunction "P$2_2") (pintype "passive"))
      (node (ref "R8") (pin "2") (pinfunction "P$2_2") (pintype "passive"))
      (node (ref "R80") (pin "2") (pinfunction "P$2_2") (pintype "passive"))
      (node (ref "R82") (pin "2") (pinfunction "P$2_2") (pintype "passive"))
      (node (ref "R83") (pin "2") (pinfunction "P$2_2") (pintype "passive"))
      (node (ref "R9") (pin "2") (pinfunction "P$2_2") (pintype "passive"))
    )
    (net (code "110") (name "VMON1") (class "Default")
      (node (ref "JP1") (pin "7") (pinfunction "7_7") (pintype "passive"))
      (node (ref "R18") (pin "1") (pinfunction "P$1_1") (pintype "passive"))
      (node (ref "R26") (pin "P$2") (pinfunction "2_P$2") (pintype "passive"))
    )
    (net (code "111") (name "VMON1_B") (class "Default")
      (node (ref "C9") (pin "2") (pinfunction "P$2_2") (pintype "passive"))
      (node (ref "R26") (pin "P$1") (pinfunction "1_P$1") (pintype "passive"))
      (node (ref "R27") (pin "P$2") (pinfunction "2_P$2") (pintype "passive"))
      (node (ref "U$1") (pin "A10") (pinfunction "A10_A10") (pintype "bidirectional"))
    )
    (net (code "112") (name "VMON2") (class "Default")
      (node (ref "JP2") (pin "7") (pinfunction "7_7") (pintype "passive"))
      (node (ref "R24") (pin "P$2") (pinfunction "2_P$2") (pintype "passive"))
      (node (ref "R54") (pin "1") (pinfunction "P$1_1") (pintype "passive"))
    )
    (net (code "113") (name "VMON2_B") (class "Default")
      (node (ref "C6") (pin "2") (pinfunction "P$2_2") (pintype "passive"))
      (node (ref "R24") (pin "P$1") (pinfunction "1_P$1") (pintype "passive"))
      (node (ref "R25") (pin "P$2") (pinfunction "2_P$2") (pintype "passive"))
      (node (ref "U$1") (pin "22/A8") (pinfunction "22/A8/T/PWM_22/A8") (pintype "bidirectional"))
    )
    (net (code "114") (name "VMON3") (class "Default")
      (node (ref "JP8") (pin "7") (pinfunction "7_7") (pintype "passive"))
      (node (ref "R22") (pin "P$2") (pinfunction "2_P$2") (pintype "passive"))
      (node (ref "R72") (pin "1") (pinfunction "P$1_1") (pintype "passive"))
    )
    (net (code "115") (name "VMON3_B") (class "Default")
      (node (ref "C4") (pin "2") (pinfunction "P$2_2") (pintype "passive"))
      (node (ref "R22") (pin "P$1") (pinfunction "1_P$1") (pintype "passive"))
      (node (ref "R23") (pin "P$2") (pinfunction "2_P$2") (pintype "passive"))
      (node (ref "U$1") (pin "20/A6") (pinfunction "20/A6/PWM_20/A6") (pintype "bidirectional"))
    )
    (net (code "116") (name "VMON4") (class "Default")
      (node (ref "JP11") (pin "7") (pinfunction "7_7") (pintype "passive"))
      (node (ref "R20") (pin "P$2") (pinfunction "2_P$2") (pintype "passive"))
      (node (ref "R90") (pin "1") (pinfunction "P$1_1") (pintype "passive"))
    )
    (net (code "117") (name "VMON4_B") (class "Default")
      (node (ref "C3") (pin "2") (pinfunction "P$2_2") (pintype "passive"))
      (node (ref "R20") (pin "P$1") (pinfunction "1_P$1") (pintype "passive"))
      (node (ref "R21") (pin "P$2") (pinfunction "2_P$2") (pintype "passive"))
      (node (ref "U$1") (pin "18/A4") (pinfunction "18/A4/T/SDA0_18/A4") (pintype "bidirectional"))
    )
    (net (code "118") (name "VSET1") (class "Default")
      (node (ref "IC1") (pin "3") (pinfunction "+IN_3") (pintype "input"))
      (node (ref "IC1") (pin "6") (pinfunction "-IN_6") (pintype "input"))
      (node (ref "IC3") (pin "1") (pinfunction "VOUTA_1") (pintype "output"))
      (node (ref "JP1") (pin "10") (pinfunction "10_10") (pintype "passive"))
      (node (ref "TP8") (pin "P$1") (pinfunction "P$1_P$1") (pintype "bidirectional"))
    )
    (net (code "119") (name "VSET2") (class "Default")
      (node (ref "IC2") (pin "3") (pinfunction "+IN_3") (pintype "input"))
      (node (ref "IC2") (pin "6") (pinfunction "-IN_6") (pintype "input"))
      (node (ref "IC3") (pin "2") (pinfunction "VOUTB_2") (pintype "output"))
      (node (ref "JP2") (pin "10") (pinfunction "10_10") (pintype "passive"))
      (node (ref "TP14") (pin "P$1") (pinfunction "P$1_P$1") (pintype "bidirectional"))
    )
    (net (code "120") (name "VSET3") (class "Default")
      (node (ref "IC3") (pin "4") (pinfunction "VOUTC_4") (pintype "output"))
      (node (ref "IC7") (pin "3") (pinfunction "+IN_3") (pintype "input"))
      (node (ref "IC7") (pin "6") (pinfunction "-IN_6") (pintype "input"))
      (node (ref "JP8") (pin "10") (pinfunction "10_10") (pintype "passive"))
      (node (ref "TP20") (pin "P$1") (pinfunction "P$1_P$1") (pintype "bidirectional"))
    )
    (net (code "121") (name "VSET4") (class "Default")
      (node (ref "IC3") (pin "5") (pinfunction "VOUTD_5") (pintype "output"))
      (node (ref "IC9") (pin "3") (pinfunction "+IN_3") (pintype "input"))
      (node (ref "IC9") (pin "6") (pinfunction "-IN_6") (pintype "input"))
      (node (ref "JP11") (pin "10") (pinfunction "10_10") (pintype "passive"))
      (node (ref "TP26") (pin "P$1") (pinfunction "P$1_P$1") (pintype "bidirectional"))
    )
    (net (code "122") (name "VUSB") (class "Default")
      (node (ref "U$1") (pin "VUSB") (pinfunction "VUSB_VUSB") (pintype "power_in"))
    )
    (net (code "123") (name "unconnected-(IC4-SDO-Pad1)") (class "Default")
      (node (ref "IC4") (pin "1") (pinfunction "SDO_1") (pintype "bidirectional"))
    )
    (net (code "124") (name "unconnected-(IC5-SDO-Pad1)") (class "Default")
      (node (ref "IC5") (pin "1") (pinfunction "SDO_1") (pintype "bidirectional"))
    )
    (net (code "125") (name "unconnected-(IC8-SDO-Pad1)") (class "Default")
      (node (ref "IC8") (pin "1") (pinfunction "SDO_1") (pintype "bidirectional"))
    )
    (net (code "126") (name "unconnected-(IC10-SDO-Pad1)") (class "Default")
      (node (ref "IC10") (pin "1") (pinfunction "SDO_1") (pintype "bidirectional"))
    )
    (net (code "127") (name "unconnected-(S1-1-PadP$1)") (class "Default")
      (node (ref "S1") (pin "P$1") (pinfunction "1_P$1") (pintype "bidirectional"))
    )
    (net (code "128") (name "unconnected-(S2-1-PadP$1)") (class "Default")
      (node (ref "S2") (pin "P$1") (pinfunction "1_P$1") (pintype "bidirectional"))
    )
    (net (code "129") (name "unconnected-(S3-1-PadP$1)") (class "Default")
      (node (ref "S3") (pin "P$1") (pinfunction "1_P$1") (pintype "bidirectional"))
    )
    (net (code "130") (name "unconnected-(S4-1-PadP$1)") (class "Default")
      (node (ref "S4") (pin "P$1") (pinfunction "1_P$1") (pintype "bidirectional"))
    )
    (net (code "131") (name "unconnected-(U$1-A14{slash}DAC-PadA14)") (class "Default")
      (node (ref "U$1") (pin "A14") (pinfunction "A14/DAC_A14") (pintype "bidirectional"))
    )
    (net (code "132") (name "unconnected-(U$1-PadPGM)") (class "Default")
      (node (ref "U$1") (pin "PGM") (pinfunction "PGM_PGM") (pintype "bidirectional"))
    )
  )
)
